# PecanPico7.net
KiCad netlist of a schematic drawn in EAGLE
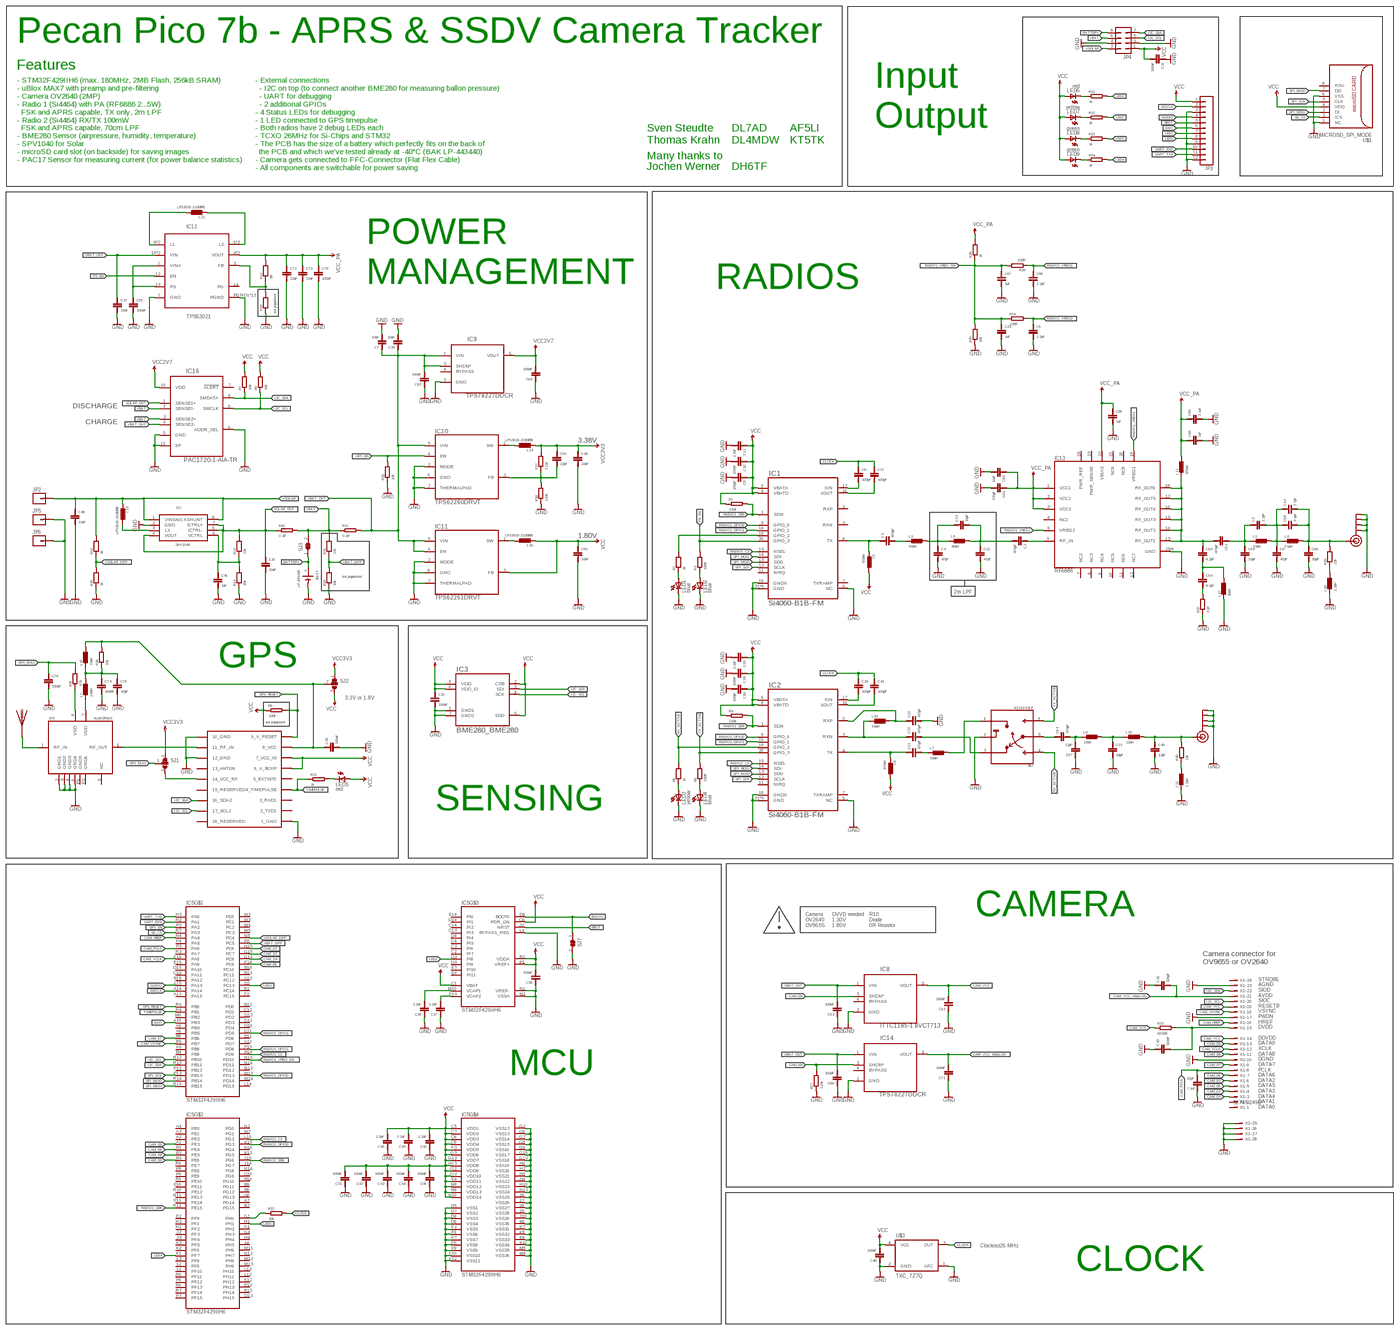
[diagram p0: schematic, sheet 1, overview]
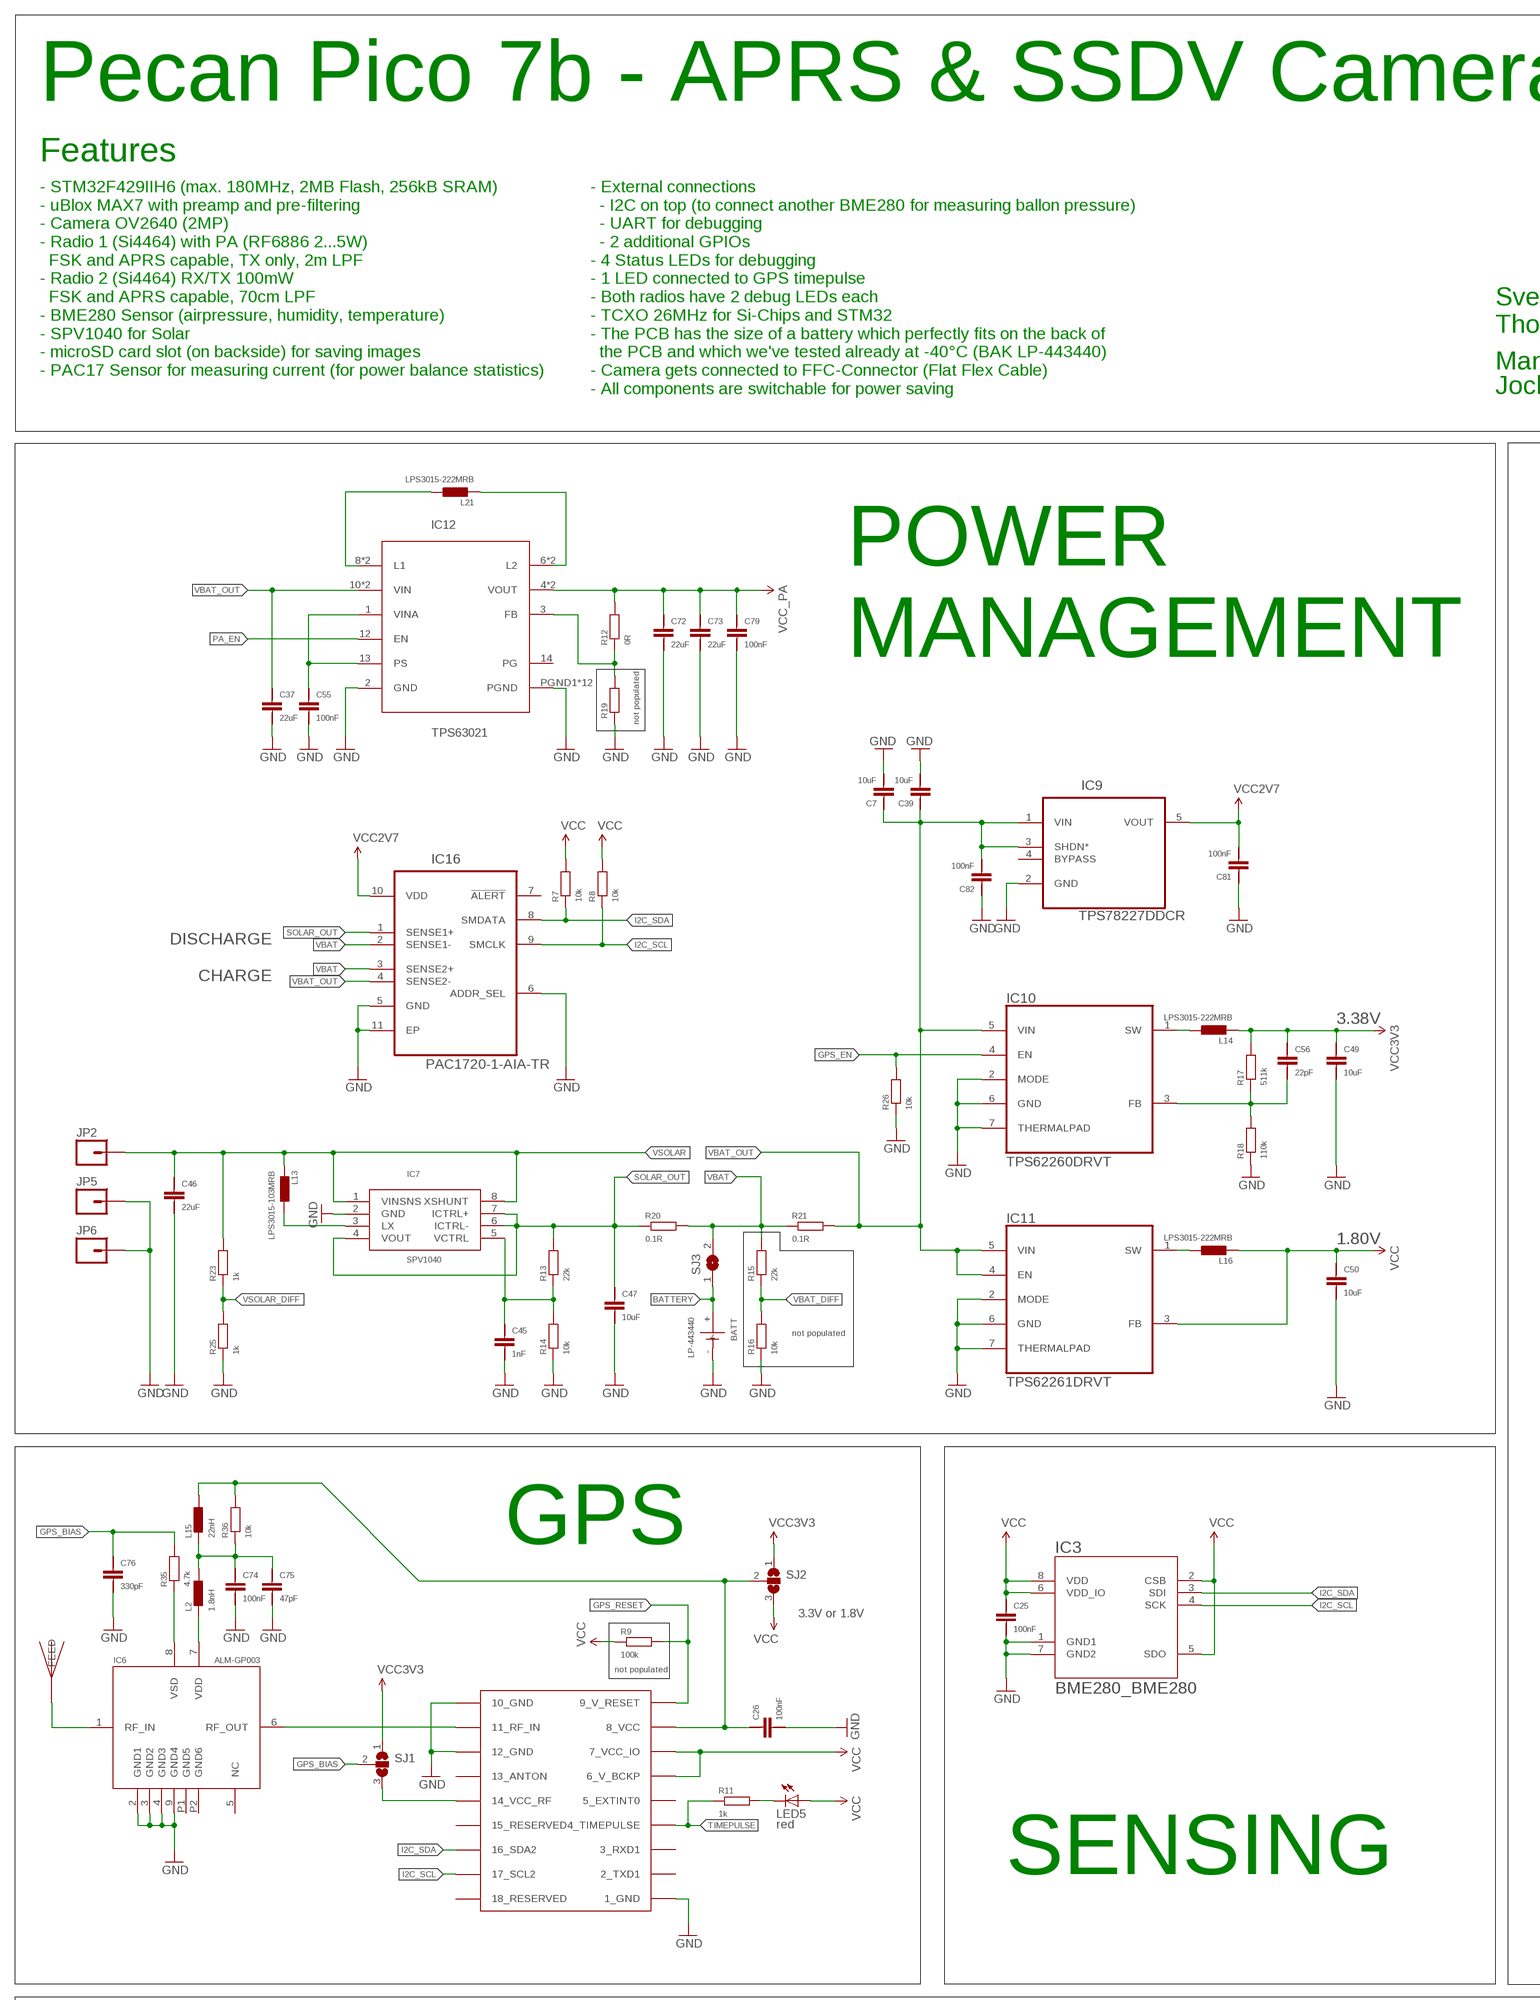
[diagram p1: schematic, sheet 1, part 1 of 4]
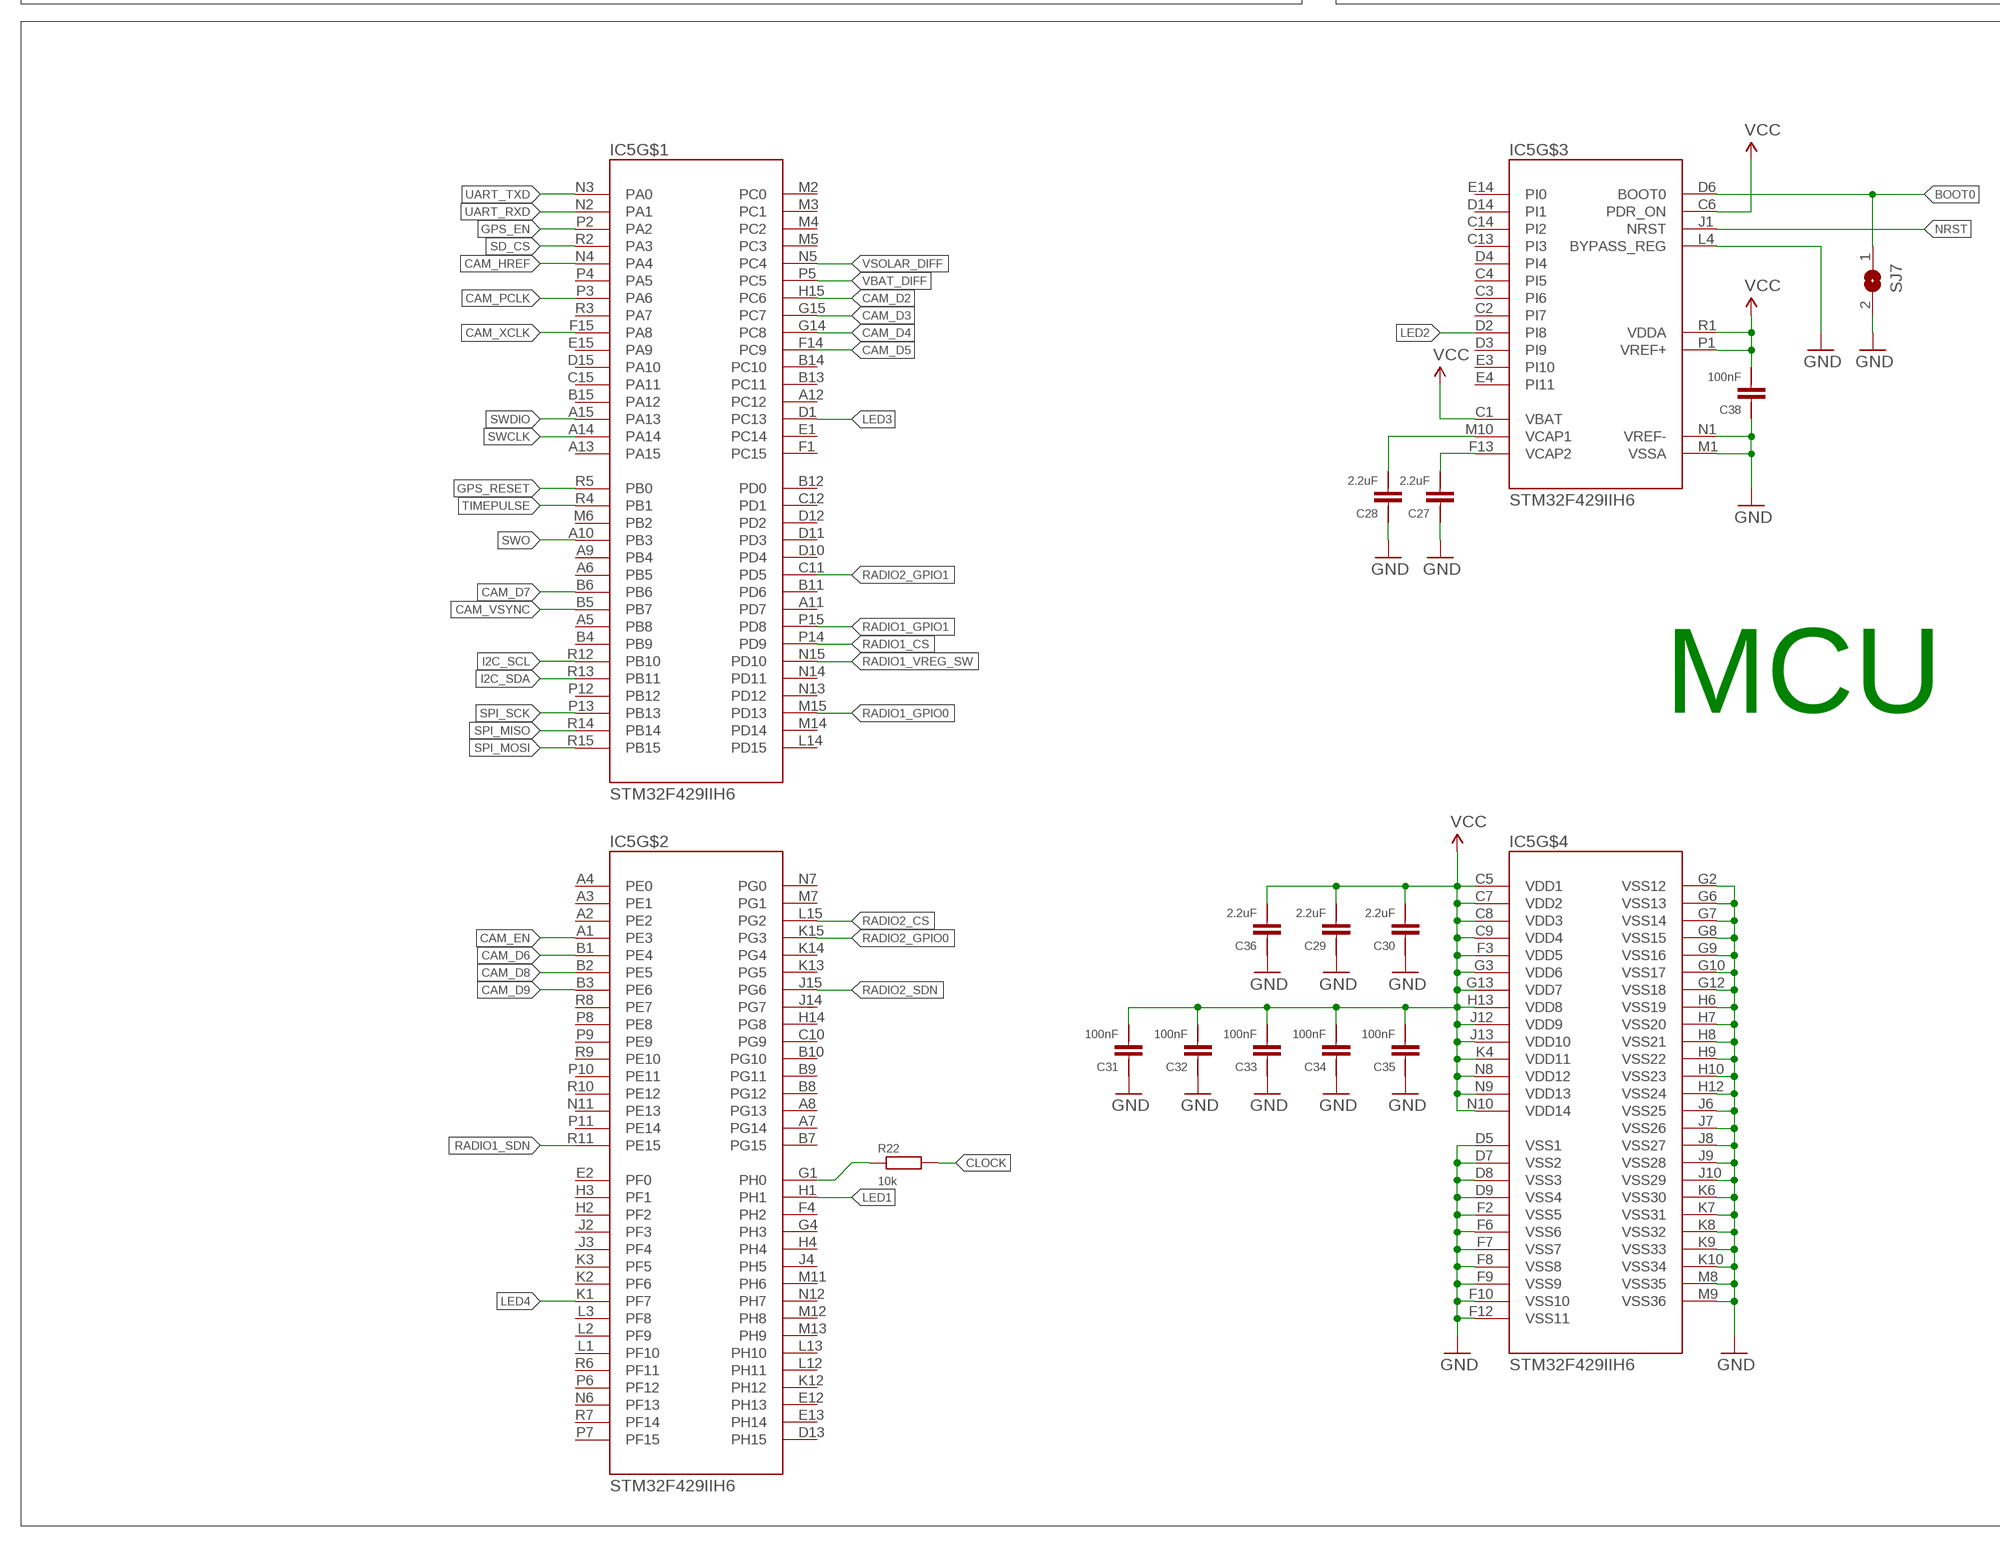
[diagram p2: schematic, sheet 1, part 2 of 4]
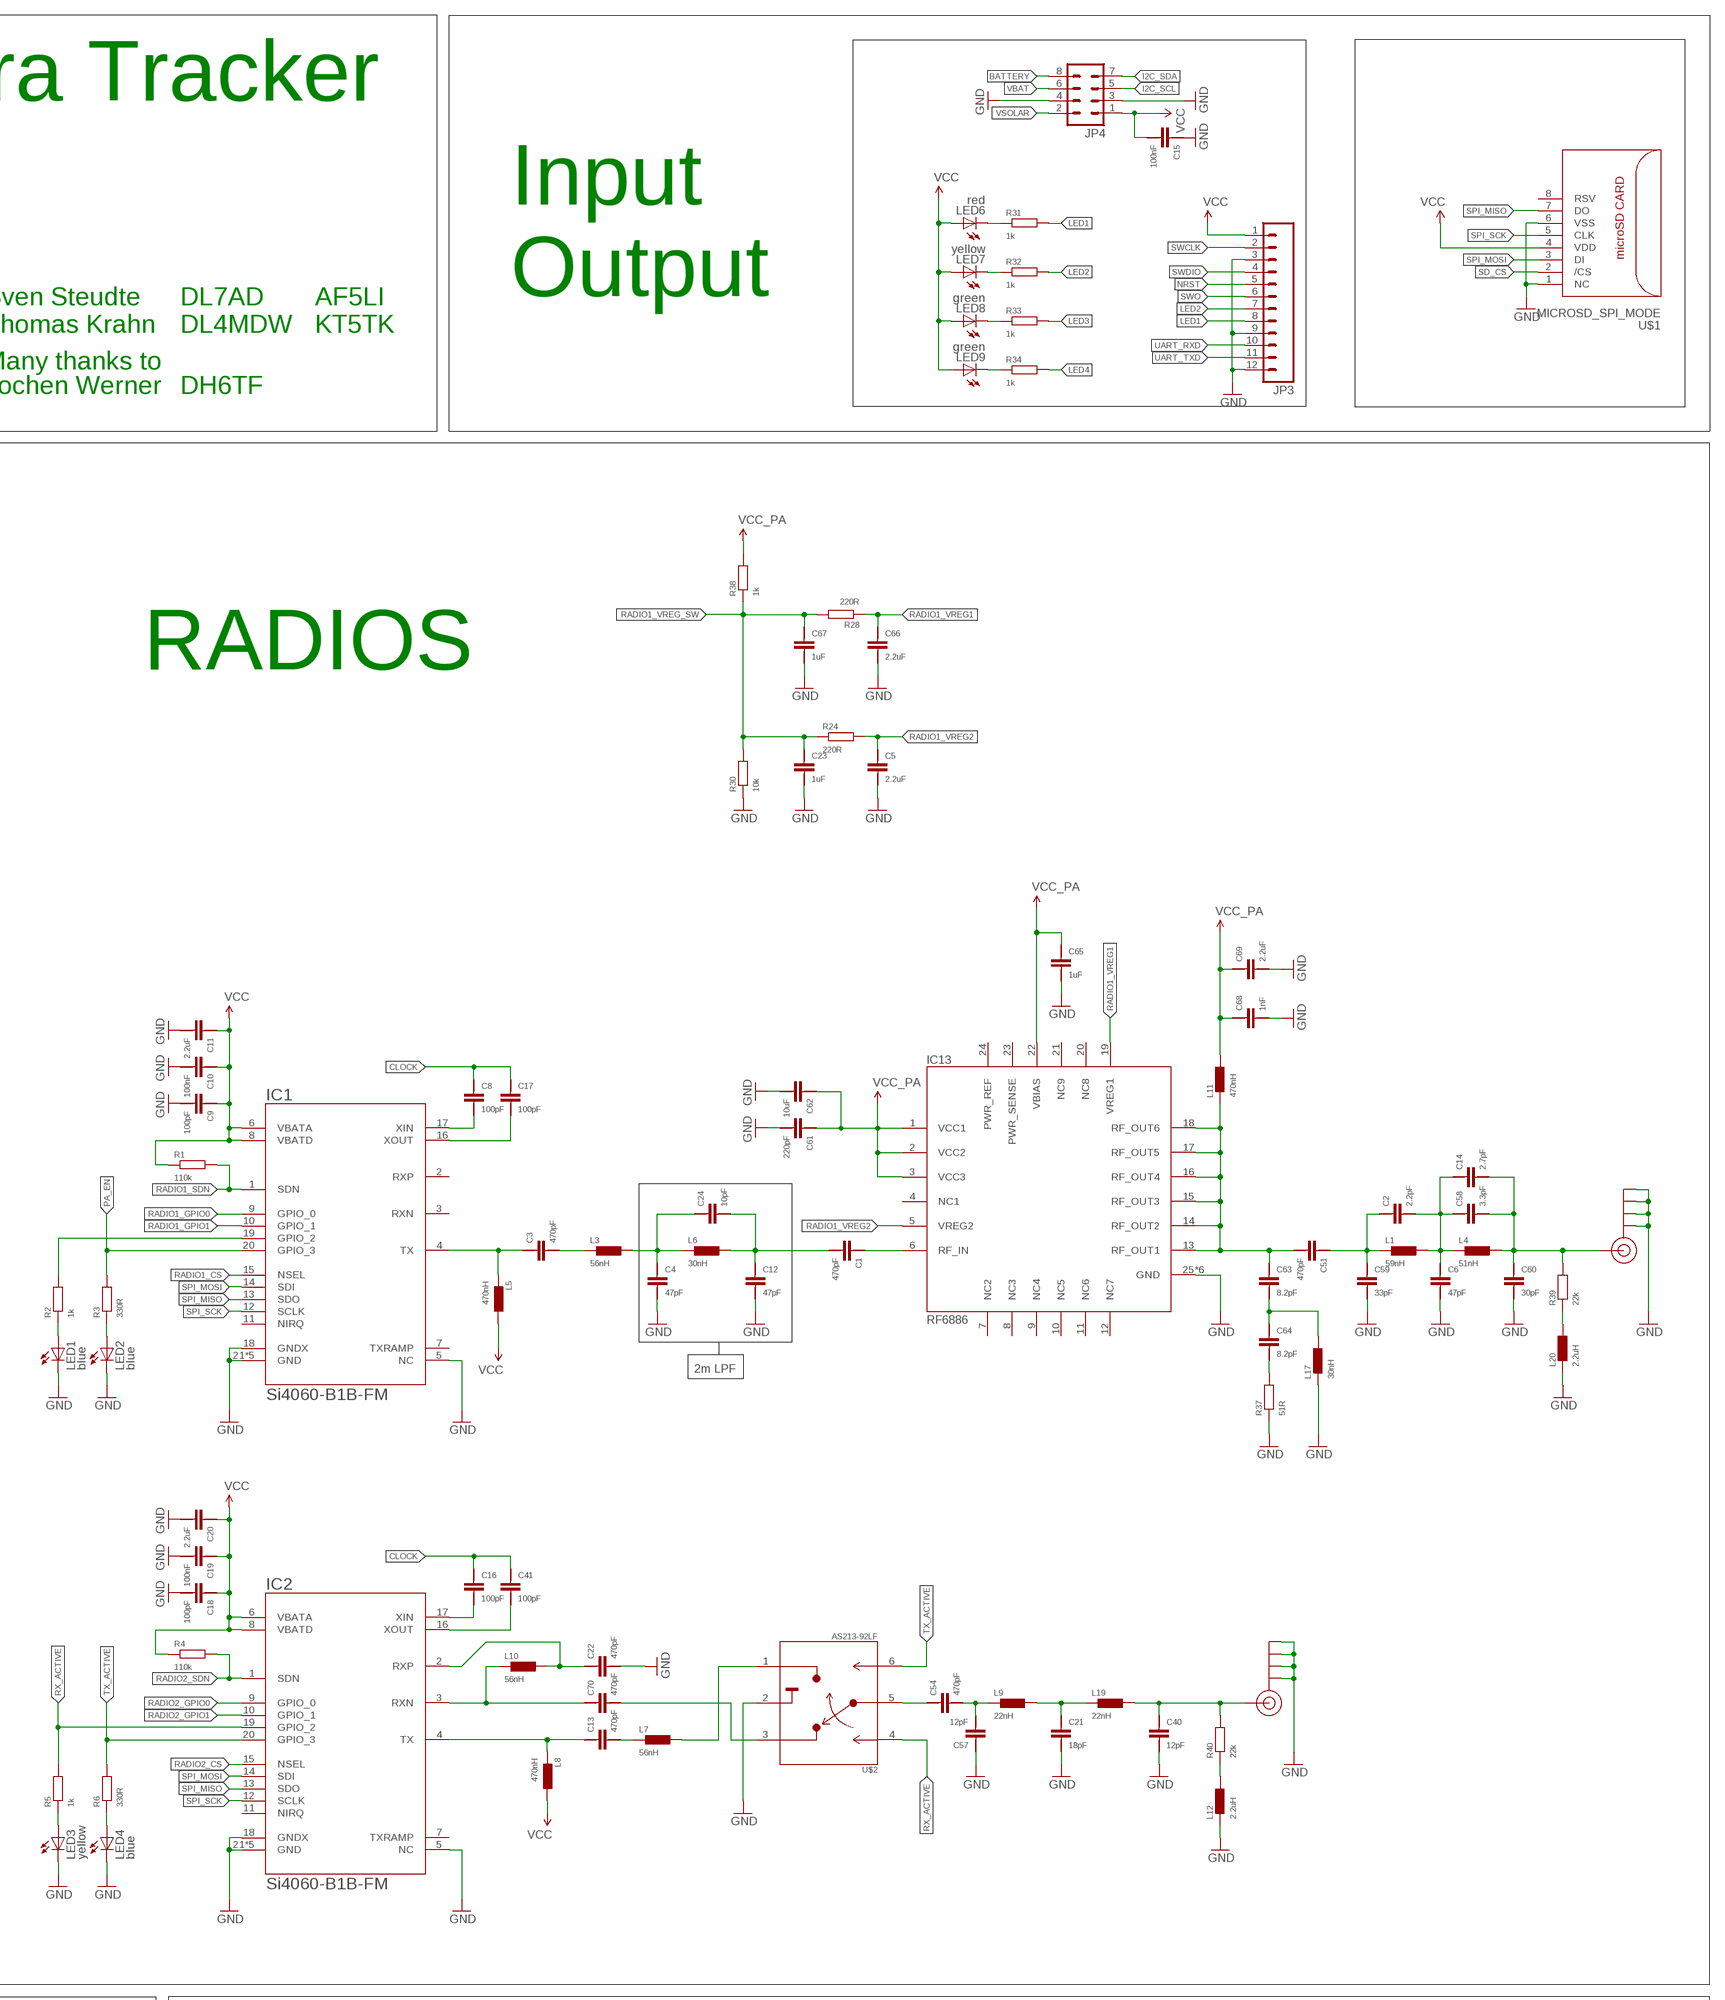
[diagram p3: schematic, sheet 1, part 3 of 4]
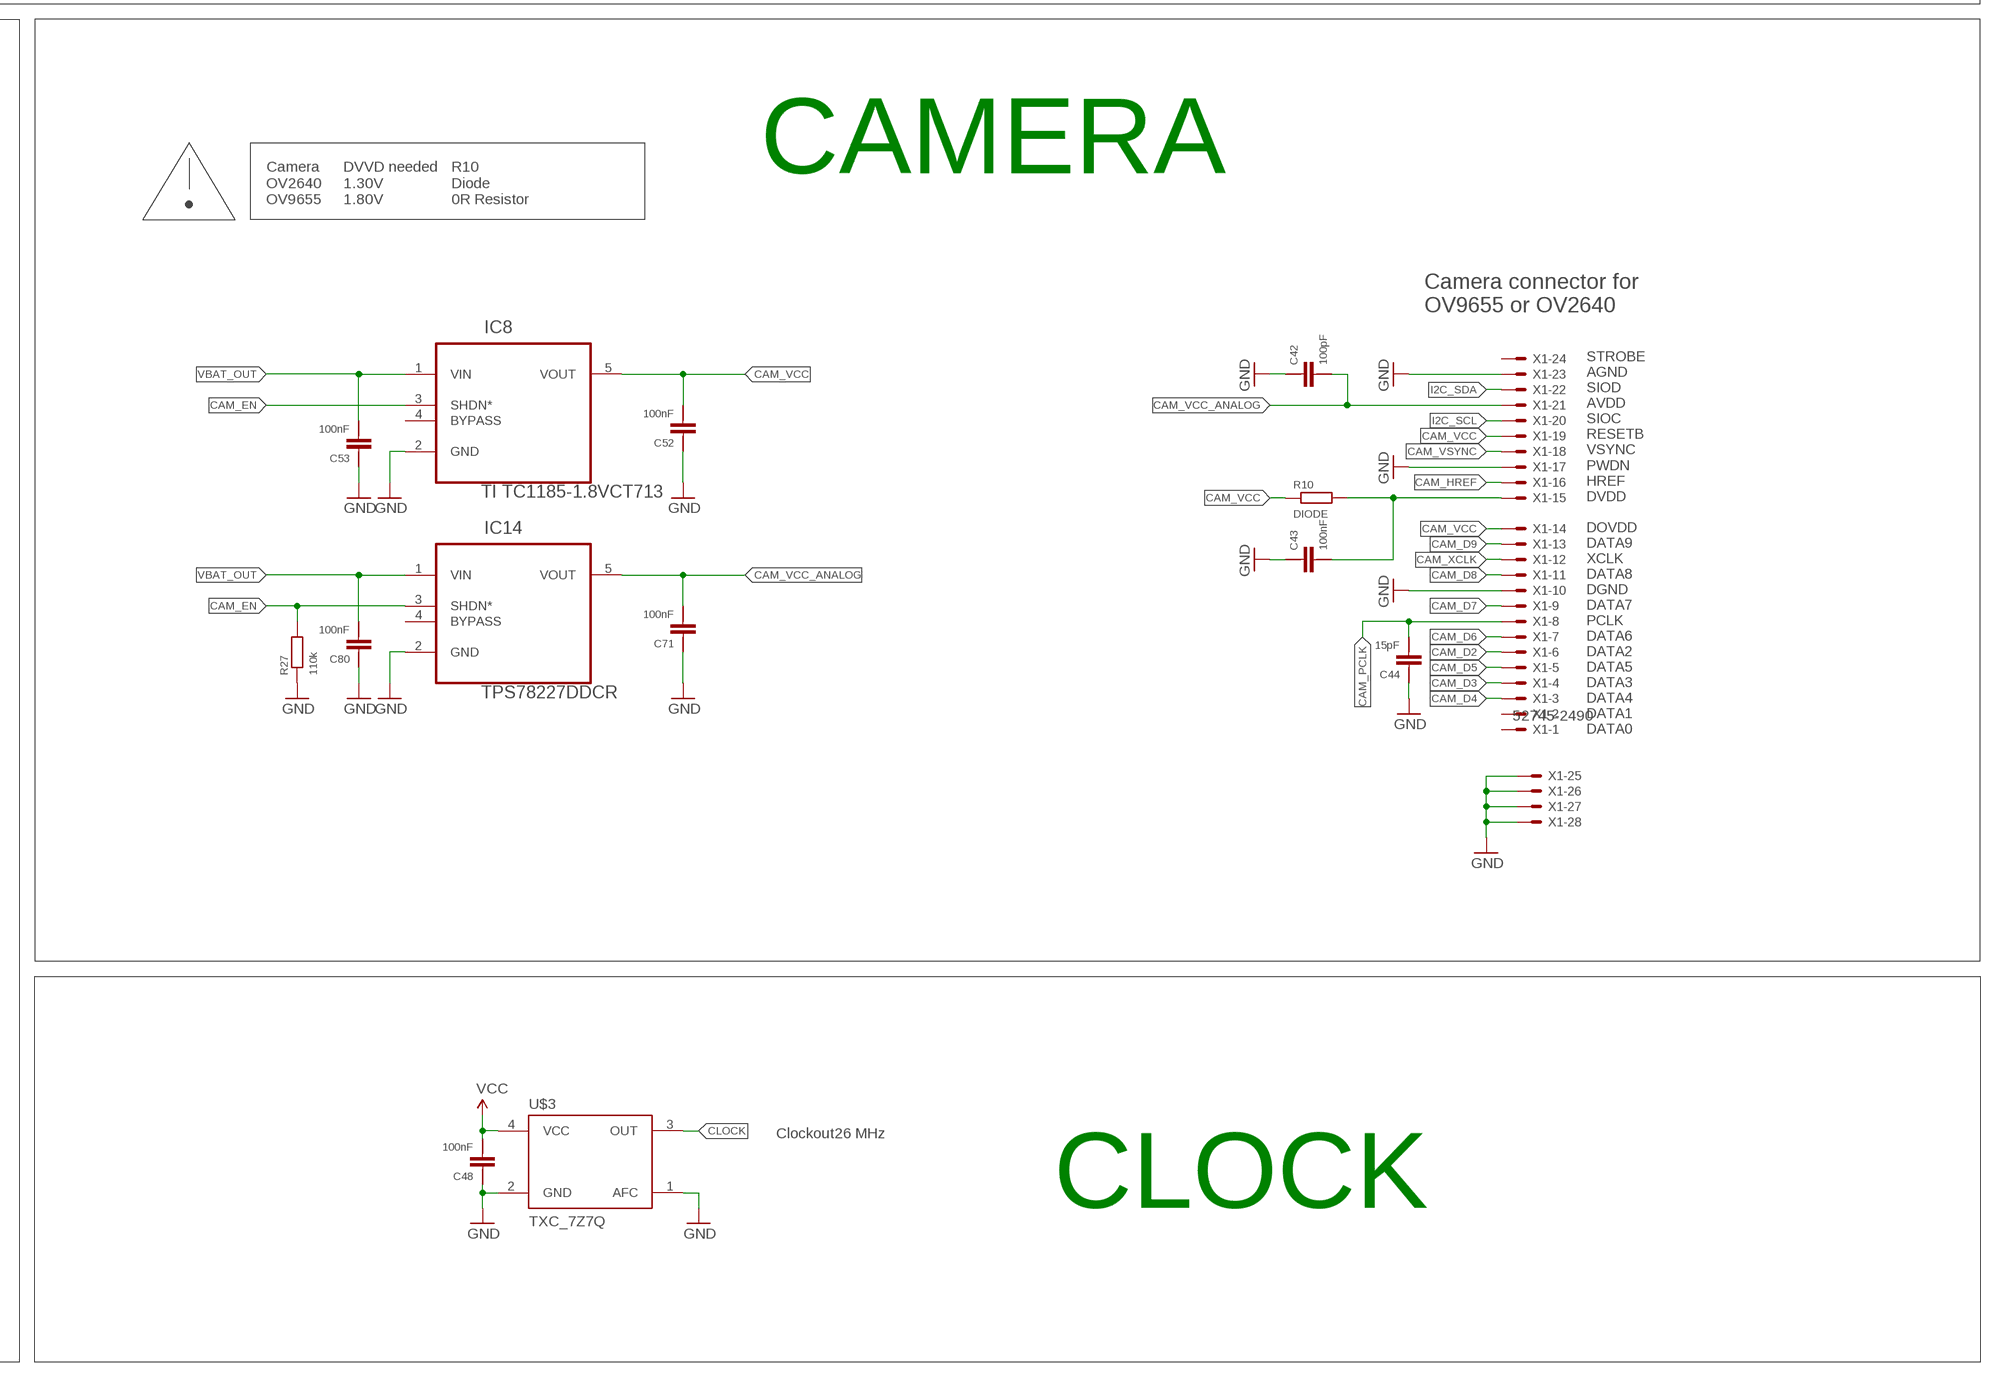
[diagram p4: schematic, sheet 1, part 4 of 4]

(export (version "E")
  (design (tool "Eeschema 10.0.6"))
  (components
    (comp (ref "BATT")
      (value "LP-443440")
      (footprint "eagle-import:LP-443440")
      (libsource (lib "eagle-import") (part "LP-443440"))
    )
    (comp (ref "C1")
      (value "470pF")
      (footprint "eagle-import:0402")
      (libsource (lib "eagle-import") (part "CAP-0402"))
    )
    (comp (ref "C2")
      (value "2.2pF")
      (footprint "eagle-import:0402")
      (libsource (lib "eagle-import") (part "CAP-0402"))
    )
    (comp (ref "C3")
      (value "470pF")
      (footprint "eagle-import:0402")
      (libsource (lib "eagle-import") (part "CAP-0402"))
    )
    (comp (ref "C4")
      (value "47pF")
      (footprint "eagle-import:0402")
      (libsource (lib "eagle-import") (part "CAP-0402"))
    )
    (comp (ref "C5")
      (value "2.2uF")
      (footprint "eagle-import:0402")
      (libsource (lib "eagle-import") (part "CAP-0402"))
    )
    (comp (ref "C6")
      (value "47pF")
      (footprint "eagle-import:0402")
      (libsource (lib "eagle-import") (part "CAP-0402"))
    )
    (comp (ref "C7")
      (value "10uF")
      (footprint "eagle-import:0805")
      (libsource (lib "eagle-import") (part "CAP-0805"))
    )
    (comp (ref "C8")
      (value "100pF")
      (footprint "eagle-import:0402")
      (libsource (lib "eagle-import") (part "CAP-0402"))
    )
    (comp (ref "C9")
      (value "100pF")
      (footprint "eagle-import:0402")
      (libsource (lib "eagle-import") (part "CAP-0402"))
    )
    (comp (ref "C10")
      (value "100nF")
      (footprint "eagle-import:0402")
      (libsource (lib "eagle-import") (part "CAP-0402"))
    )
    (comp (ref "C11")
      (value "2.2uF")
      (footprint "eagle-import:0402")
      (libsource (lib "eagle-import") (part "CAP-0402"))
    )
    (comp (ref "C12")
      (value "47pF")
      (footprint "eagle-import:0402")
      (libsource (lib "eagle-import") (part "CAP-0402"))
    )
    (comp (ref "C13")
      (value "470pF")
      (footprint "eagle-import:0402")
      (libsource (lib "eagle-import") (part "CAP-0402"))
    )
    (comp (ref "C14")
      (value "2.7pF")
      (footprint "eagle-import:0402")
      (libsource (lib "eagle-import") (part "CAP-0402"))
    )
    (comp (ref "C15")
      (value "100nF")
      (footprint "eagle-import:0402")
      (libsource (lib "eagle-import") (part "CAP-0402"))
    )
    (comp (ref "C16")
      (value "100pF")
      (footprint "eagle-import:0402")
      (libsource (lib "eagle-import") (part "CAP-0402"))
    )
    (comp (ref "C17")
      (value "100pF")
      (footprint "eagle-import:0402")
      (libsource (lib "eagle-import") (part "CAP-0402"))
    )
    (comp (ref "C18")
      (value "100pF")
      (footprint "eagle-import:0402")
      (libsource (lib "eagle-import") (part "CAP-0402"))
    )
    (comp (ref "C19")
      (value "100nF")
      (footprint "eagle-import:0402")
      (libsource (lib "eagle-import") (part "CAP-0402"))
    )
    (comp (ref "C20")
      (value "2.2uF")
      (footprint "eagle-import:0402")
      (libsource (lib "eagle-import") (part "CAP-0402"))
    )
    (comp (ref "C21")
      (value "18pF")
      (footprint "eagle-import:0402")
      (libsource (lib "eagle-import") (part "CAP-0402"))
    )
    (comp (ref "C22")
      (value "470pF")
      (footprint "eagle-import:0402")
      (libsource (lib "eagle-import") (part "CAP-0402"))
    )
    (comp (ref "C23")
      (value "1uF")
      (footprint "eagle-import:0402")
      (libsource (lib "eagle-import") (part "CAP-0402"))
    )
    (comp (ref "C24")
      (value "10pF")
      (footprint "eagle-import:0402")
      (libsource (lib "eagle-import") (part "CAP-0402"))
    )
    (comp (ref "C25")
      (value "100nF")
      (footprint "eagle-import:0402")
      (libsource (lib "eagle-import") (part "CAP-0402"))
    )
    (comp (ref "C26")
      (value "100nF")
      (footprint "eagle-import:0402")
      (libsource (lib "eagle-import") (part "CAP-0402"))
    )
    (comp (ref "C27")
      (value "2.2uF")
      (footprint "eagle-import:0402")
      (libsource (lib "eagle-import") (part "CAP-0402"))
    )
    (comp (ref "C28")
      (value "2.2uF")
      (footprint "eagle-import:0402")
      (libsource (lib "eagle-import") (part "CAP-0402"))
    )
    (comp (ref "C29")
      (value "2.2uF")
      (footprint "eagle-import:0402")
      (libsource (lib "eagle-import") (part "CAP-0402"))
    )
    (comp (ref "C30")
      (value "2.2uF")
      (footprint "eagle-import:0402")
      (libsource (lib "eagle-import") (part "CAP-0402"))
    )
    (comp (ref "C31")
      (value "100nF")
      (footprint "eagle-import:0402")
      (libsource (lib "eagle-import") (part "CAP-0402"))
    )
    (comp (ref "C32")
      (value "100nF")
      (footprint "eagle-import:0402")
      (libsource (lib "eagle-import") (part "CAP-0402"))
    )
    (comp (ref "C33")
      (value "100nF")
      (footprint "eagle-import:0402")
      (libsource (lib "eagle-import") (part "CAP-0402"))
    )
    (comp (ref "C34")
      (value "100nF")
      (footprint "eagle-import:0402")
      (libsource (lib "eagle-import") (part "CAP-0402"))
    )
    (comp (ref "C35")
      (value "100nF")
      (footprint "eagle-import:0402")
      (libsource (lib "eagle-import") (part "CAP-0402"))
    )
    (comp (ref "C36")
      (value "2.2uF")
      (footprint "eagle-import:0402")
      (libsource (lib "eagle-import") (part "CAP-0402"))
    )
    (comp (ref "C37")
      (value "22uF")
      (footprint "eagle-import:0805")
      (libsource (lib "eagle-import") (part "CAP-0805"))
    )
    (comp (ref "C38")
      (value "100nF")
      (footprint "eagle-import:0402")
      (libsource (lib "eagle-import") (part "CAP-0402"))
    )
    (comp (ref "C39")
      (value "10uF")
      (footprint "eagle-import:0805")
      (libsource (lib "eagle-import") (part "CAP-0805"))
    )
    (comp (ref "C40")
      (value "12pF")
      (footprint "eagle-import:0402")
      (libsource (lib "eagle-import") (part "CAP-0402"))
    )
    (comp (ref "C41")
      (value "100pF")
      (footprint "eagle-import:0402")
      (libsource (lib "eagle-import") (part "CAP-0402"))
    )
    (comp (ref "C42")
      (value "100pF")
      (footprint "eagle-import:0402")
      (libsource (lib "eagle-import") (part "CAP-0402"))
    )
    (comp (ref "C43")
      (value "100nF")
      (footprint "eagle-import:0402")
      (libsource (lib "eagle-import") (part "CAP-0402"))
    )
    (comp (ref "C44")
      (value "15pF")
      (footprint "eagle-import:0402")
      (libsource (lib "eagle-import") (part "CAP-0402"))
    )
    (comp (ref "C45")
      (value "1nF")
      (footprint "eagle-import:0402")
      (libsource (lib "eagle-import") (part "CAP-0402"))
    )
    (comp (ref "C46")
      (value "22uF")
      (footprint "eagle-import:0805")
      (libsource (lib "eagle-import") (part "CAP-0805"))
    )
    (comp (ref "C47")
      (value "10uF")
      (footprint "eagle-import:0805")
      (libsource (lib "eagle-import") (part "CAP-0805"))
    )
    (comp (ref "C48")
      (value "100nF")
      (footprint "eagle-import:0402")
      (libsource (lib "eagle-import") (part "CAP-0402"))
    )
    (comp (ref "C49")
      (value "10uF")
      (footprint "eagle-import:0805")
      (libsource (lib "eagle-import") (part "CAP-0805"))
    )
    (comp (ref "C50")
      (value "10uF")
      (footprint "eagle-import:0805")
      (libsource (lib "eagle-import") (part "CAP-0805"))
    )
    (comp (ref "C51")
      (value "470pF")
      (footprint "eagle-import:0402")
      (libsource (lib "eagle-import") (part "CAP-0402"))
    )
    (comp (ref "C52")
      (value "100nF")
      (footprint "eagle-import:0402")
      (libsource (lib "eagle-import") (part "CAP-0402"))
    )
    (comp (ref "C53")
      (value "100nF")
      (footprint "eagle-import:0402")
      (libsource (lib "eagle-import") (part "CAP-0402"))
    )
    (comp (ref "C54")
      (value "470pF")
      (footprint "eagle-import:0402")
      (libsource (lib "eagle-import") (part "CAP-0402"))
    )
    (comp (ref "C55")
      (value "100nF")
      (footprint "eagle-import:0402")
      (libsource (lib "eagle-import") (part "CAP-0402"))
    )
    (comp (ref "C56")
      (value "22pF")
      (footprint "eagle-import:0402")
      (libsource (lib "eagle-import") (part "CAP-0402"))
    )
    (comp (ref "C57")
      (value "12pF")
      (footprint "eagle-import:0402")
      (libsource (lib "eagle-import") (part "CAP-0402"))
    )
    (comp (ref "C58")
      (value "3.3pF")
      (footprint "eagle-import:0402")
      (libsource (lib "eagle-import") (part "CAP-0402"))
    )
    (comp (ref "C59")
      (value "33pF")
      (footprint "eagle-import:0402")
      (libsource (lib "eagle-import") (part "CAP-0402"))
    )
    (comp (ref "C60")
      (value "30pF")
      (footprint "eagle-import:0402")
      (libsource (lib "eagle-import") (part "CAP-0402"))
    )
    (comp (ref "C61")
      (value "220pF")
      (footprint "eagle-import:0402")
      (libsource (lib "eagle-import") (part "CAP-0402"))
    )
    (comp (ref "C62")
      (value "10uF")
      (footprint "eagle-import:0805")
      (libsource (lib "eagle-import") (part "CAP-0805"))
    )
    (comp (ref "C63")
      (value "8.2pF")
      (footprint "eagle-import:0402")
      (libsource (lib "eagle-import") (part "CAP-0402"))
    )
    (comp (ref "C64")
      (value "8.2pF")
      (footprint "eagle-import:0402")
      (libsource (lib "eagle-import") (part "CAP-0402"))
    )
    (comp (ref "C65")
      (value "1uF")
      (footprint "eagle-import:0402")
      (libsource (lib "eagle-import") (part "CAP-0402"))
    )
    (comp (ref "C66")
      (value "2.2uF")
      (footprint "eagle-import:0402")
      (libsource (lib "eagle-import") (part "CAP-0402"))
    )
    (comp (ref "C67")
      (value "1uF")
      (footprint "eagle-import:0402")
      (libsource (lib "eagle-import") (part "CAP-0402"))
    )
    (comp (ref "C68")
      (value "1nF")
      (footprint "eagle-import:0402")
      (libsource (lib "eagle-import") (part "CAP-0402"))
    )
    (comp (ref "C69")
      (value "2.2uF")
      (footprint "eagle-import:0402")
      (libsource (lib "eagle-import") (part "CAP-0402"))
    )
    (comp (ref "C70")
      (value "470pF")
      (footprint "eagle-import:0402")
      (libsource (lib "eagle-import") (part "CAP-0402"))
    )
    (comp (ref "C71")
      (value "100nF")
      (footprint "eagle-import:0402")
      (libsource (lib "eagle-import") (part "CAP-0402"))
    )
    (comp (ref "C72")
      (value "22uF")
      (footprint "eagle-import:0805")
      (libsource (lib "eagle-import") (part "CAP-0805"))
    )
    (comp (ref "C73")
      (value "22uF")
      (footprint "eagle-import:0805")
      (libsource (lib "eagle-import") (part "CAP-0805"))
    )
    (comp (ref "C74")
      (value "100nF")
      (footprint "eagle-import:0402")
      (libsource (lib "eagle-import") (part "CAP-0402"))
    )
    (comp (ref "C75")
      (value "47pF")
      (footprint "eagle-import:0402")
      (libsource (lib "eagle-import") (part "CAP-0402"))
    )
    (comp (ref "C76")
      (value "330pF")
      (footprint "eagle-import:0402")
      (libsource (lib "eagle-import") (part "CAP-0402"))
    )
    (comp (ref "C79")
      (value "100nF")
      (footprint "eagle-import:0402")
      (libsource (lib "eagle-import") (part "CAP-0402"))
    )
    (comp (ref "C80")
      (value "100nF")
      (footprint "eagle-import:0402")
      (libsource (lib "eagle-import") (part "CAP-0402"))
    )
    (comp (ref "C81")
      (value "100nF")
      (footprint "eagle-import:0402")
      (libsource (lib "eagle-import") (part "CAP-0402"))
    )
    (comp (ref "C82")
      (value "100nF")
      (footprint "eagle-import:0402")
      (libsource (lib "eagle-import") (part "CAP-0402"))
    )
    (comp (ref "IC1")
      (value "Si4060-B1B-FM")
      (footprint "eagle-import:QFN-20")
      (libsource (lib "eagle-import") (part "SI4463/4"))
    )
    (comp (ref "IC2")
      (value "Si4060-B1B-FM")
      (footprint "eagle-import:QFN-20")
      (libsource (lib "eagle-import") (part "SI4463/4"))
    )
    (comp (ref "IC3")
      (value "BME280_BME280")
      (footprint "eagle-import:BME280_BME280")
      (libsource (lib "eagle-import") (part "BME280_BME280"))
    )
    (comp (ref "IC4")
      (value "uBlox MAX7/8")
      (footprint "eagle-import:UBLOX_MAX-6")
      (libsource (lib "eagle-import") (part "UBLOX_MAX-6"))
    )
    (comp (ref "IC5")
      (value "STM32F429IIH6")
      (footprint "eagle-import:UFBGA176")
      (libsource (lib "eagle-import") (part "STM32F429IIH6"))
    )
    (comp (ref "IC6")
      (value "ALM-GP003")
      (footprint "eagle-import:ALM-GP003")
      (libsource (lib "eagle-import") (part "ALM-GP003"))
    )
    (comp (ref "IC7")
      (value "SPV1040")
      (footprint "eagle-import:TSSOP8")
      (libsource (lib "eagle-import") (part "SPV1040"))
    )
    (comp (ref "IC8")
      (value "TI TC1185-1.8VCT713")
      (footprint "eagle-import:SOT95P290X145-5N")
      (fields (field (name "MPN") "TC1185-1.8VCT713"))
      (libsource (lib "eagle-import") (part "TC1185-1.8VCT713"))
    )
    (comp (ref "IC9")
      (value "TPS78227DDCR")
      (footprint "eagle-import:SOT95P290X145-5N")
      (fields (field (name "MPN") "TC1185-1.8VCT713"))
      (libsource (lib "eagle-import") (part "TC1185-1.8VCT713"))
    )
    (comp (ref "IC10")
      (value "TPS62260DRVT")
      (footprint "eagle-import:SON65P210X210X80-7N")
      (libsource (lib "eagle-import") (part "TPS62260DRVT"))
    )
    (comp (ref "IC11")
      (value "TPS62261DRVT")
      (footprint "eagle-import:SON65P210X210X80-7N")
      (fields (field (name "MPN") "TPS62260DRVT"))
      (libsource (lib "eagle-import") (part "TPS62260DRVT"))
    )
    (comp (ref "IC12")
      (value "TPS63021")
      (footprint "eagle-import:QFN-14")
      (libsource (lib "eagle-import") (part "TPS63020"))
    )
    (comp (ref "IC13")
      (value "RF6886")
      (footprint "eagle-import:QFN-24")
      (libsource (lib "eagle-import") (part "RF6886"))
    )
    (comp (ref "IC14")
      (value "TPS78227DDCR")
      (footprint "eagle-import:SOT95P290X145-5N")
      (fields (field (name "MPN") "TC1185-1.8VCT713"))
      (libsource (lib "eagle-import") (part "TC1185-1.8VCT713"))
    )
    (comp (ref "IC16")
      (value "PAC1720-1-AIA-TR")
      (footprint "eagle-import:DFN300X300X90-11N")
      (libsource (lib "eagle-import") (part "PAC1720-1-AIA-TR"))
    )
    (comp (ref "J$1")
      (value "SMA_EDGE")
      (footprint "eagle-import:SMA-EDGE")
      (libsource (lib "eagle-import") (part "SMA_EDGE"))
    )
    (comp (ref "J$2")
      (value "SMA_EDGE")
      (footprint "eagle-import:SMA-EDGE")
      (libsource (lib "eagle-import") (part "SMA_EDGE"))
    )
    (comp (ref "JP2")
      (value "M01SMD")
      (footprint "eagle-import:LUXEON-PAD")
      (libsource (lib "eagle-import") (part "M01SMD"))
    )
    (comp (ref "JP3")
      (value "M12PTH")
      (footprint "eagle-import:1X12")
      (libsource (lib "eagle-import") (part "M12PTH"))
    )
    (comp (ref "JP4")
      (value "M04X2SMD")
      (footprint "eagle-import:2X4_2")
      (libsource (lib "eagle-import") (part "M04X2SMD"))
    )
    (comp (ref "JP5")
      (value "M01SMD")
      (footprint "eagle-import:LUXEON-PAD")
      (libsource (lib "eagle-import") (part "M01SMD"))
    )
    (comp (ref "JP6")
      (value "M01SMD")
      (footprint "eagle-import:LUXEON-PAD")
      (libsource (lib "eagle-import") (part "M01SMD"))
    )
    (comp (ref "L1")
      (value "59nH")
      (footprint "eagle-import:0603@1")
      (libsource (lib "eagle-import") (part "IND-04020603"))
    )
    (comp (ref "L2")
      (value "1.8nH")
      (footprint "eagle-import:0402")
      (libsource (lib "eagle-import") (part "IND-0402"))
    )
    (comp (ref "L3")
      (value "56nH")
      (footprint "eagle-import:0402")
      (libsource (lib "eagle-import") (part "IND-0402"))
    )
    (comp (ref "L4")
      (value "51nH")
      (footprint "eagle-import:0603@1")
      (libsource (lib "eagle-import") (part "IND-04020603"))
    )
    (comp (ref "L5")
      (value "470nH")
      (footprint "eagle-import:0805@1")
      (libsource (lib "eagle-import") (part "IND-04020805"))
    )
    (comp (ref "L6")
      (value "30nH")
      (footprint "eagle-import:0402")
      (libsource (lib "eagle-import") (part "IND-0402"))
    )
    (comp (ref "L7")
      (value "56nH")
      (footprint "eagle-import:0402")
      (libsource (lib "eagle-import") (part "IND-0402"))
    )
    (comp (ref "L8")
      (value "470nH")
      (footprint "eagle-import:0805@1")
      (libsource (lib "eagle-import") (part "IND-04020805"))
    )
    (comp (ref "L9")
      (value "22nH")
      (footprint "eagle-import:0402")
      (libsource (lib "eagle-import") (part "IND-0402"))
    )
    (comp (ref "L10")
      (value "56nH")
      (footprint "eagle-import:0402")
      (libsource (lib "eagle-import") (part "IND-0402"))
    )
    (comp (ref "L11")
      (value "470nH")
      (footprint "eagle-import:0805@1")
      (libsource (lib "eagle-import") (part "IND-04020805"))
    )
    (comp (ref "L12")
      (value "2.2uH")
      (footprint "eagle-import:0402")
      (libsource (lib "eagle-import") (part "IND-0402"))
    )
    (comp (ref "L13")
      (value "LPS3015-103MRB")
      (footprint "eagle-import:LPS3015")
      (libsource (lib "eagle-import") (part "IND-LPS3015"))
    )
    (comp (ref "L14")
      (value "LPS3015-222MRB")
      (footprint "eagle-import:LPS3015")
      (libsource (lib "eagle-import") (part "IND-LPS3015"))
    )
    (comp (ref "L15")
      (value "22nH")
      (footprint "eagle-import:0402")
      (libsource (lib "eagle-import") (part "IND-0402"))
    )
    (comp (ref "L16")
      (value "LPS3015-222MRB")
      (footprint "eagle-import:LPS3015")
      (libsource (lib "eagle-import") (part "IND-LPS3015"))
    )
    (comp (ref "L17")
      (value "30nH")
      (footprint "eagle-import:0603@1")
      (libsource (lib "eagle-import") (part "IND-04020603"))
    )
    (comp (ref "L19")
      (value "22nH")
      (footprint "eagle-import:0402")
      (libsource (lib "eagle-import") (part "IND-0402"))
    )
    (comp (ref "L20")
      (value "2.2uH")
      (footprint "eagle-import:0402")
      (libsource (lib "eagle-import") (part "IND-0402"))
    )
    (comp (ref "L21")
      (value "LPS3015-222MRB")
      (footprint "eagle-import:LPS3015")
      (libsource (lib "eagle-import") (part "IND-LPS3015"))
    )
    (comp (ref "LED1")
      (value "blue")
      (footprint "eagle-import:LED-0603")
      (libsource (lib "eagle-import") (part "LED0603"))
    )
    (comp (ref "LED2")
      (value "blue")
      (footprint "eagle-import:LED-0603")
      (libsource (lib "eagle-import") (part "LED0603"))
    )
    (comp (ref "LED3")
      (value "yellow")
      (footprint "eagle-import:LED-0603")
      (libsource (lib "eagle-import") (part "LED0603"))
    )
    (comp (ref "LED4")
      (value "blue")
      (footprint "eagle-import:LED-0603")
      (libsource (lib "eagle-import") (part "LED0603"))
    )
    (comp (ref "LED5")
      (value "red")
      (footprint "eagle-import:LED-0603")
      (libsource (lib "eagle-import") (part "LED0603"))
    )
    (comp (ref "LED6")
      (value "red")
      (footprint "eagle-import:LED-0603")
      (libsource (lib "eagle-import") (part "LED0603"))
    )
    (comp (ref "LED7")
      (value "yellow")
      (footprint "eagle-import:LED-0603")
      (libsource (lib "eagle-import") (part "LED0603"))
    )
    (comp (ref "LED8")
      (value "green")
      (footprint "eagle-import:LED-0603")
      (libsource (lib "eagle-import") (part "LED0603"))
    )
    (comp (ref "LED9")
      (value "green")
      (footprint "eagle-import:LED-0603")
      (libsource (lib "eagle-import") (part "LED0603"))
    )
    (comp (ref "R1")
      (value "110k")
      (footprint "eagle-import:0402")
      (libsource (lib "eagle-import") (part "RES-0402"))
    )
    (comp (ref "R2")
      (value "1k")
      (footprint "eagle-import:0402")
      (libsource (lib "eagle-import") (part "RES-0402"))
    )
    (comp (ref "R3")
      (value "330R")
      (footprint "eagle-import:0402")
      (libsource (lib "eagle-import") (part "RES-0402"))
    )
    (comp (ref "R4")
      (value "110k")
      (footprint "eagle-import:0402")
      (libsource (lib "eagle-import") (part "RES-0402"))
    )
    (comp (ref "R5")
      (value "1k")
      (footprint "eagle-import:0402")
      (libsource (lib "eagle-import") (part "RES-0402"))
    )
    (comp (ref "R6")
      (value "330R")
      (footprint "eagle-import:0402")
      (libsource (lib "eagle-import") (part "RES-0402"))
    )
    (comp (ref "R7")
      (value "10k")
      (footprint "eagle-import:0402")
      (libsource (lib "eagle-import") (part "RES-0402"))
    )
    (comp (ref "R8")
      (value "10k")
      (footprint "eagle-import:0402")
      (libsource (lib "eagle-import") (part "RES-0402"))
    )
    (comp (ref "R9")
      (value "100k")
      (footprint "eagle-import:0402")
      (libsource (lib "eagle-import") (part "RES-0402"))
    )
    (comp (ref "R10")
      (value "DIODE")
      (footprint "eagle-import:0402")
      (libsource (lib "eagle-import") (part "RES-0402"))
    )
    (comp (ref "R11")
      (value "1k")
      (footprint "eagle-import:0402")
      (libsource (lib "eagle-import") (part "RES-0402"))
    )
    (comp (ref "R12")
      (value "0R")
      (footprint "eagle-import:0402")
      (libsource (lib "eagle-import") (part "RES-0402"))
    )
    (comp (ref "R13")
      (value "22k")
      (footprint "eagle-import:0402")
      (libsource (lib "eagle-import") (part "RES-0402"))
    )
    (comp (ref "R14")
      (value "10k")
      (footprint "eagle-import:0402")
      (libsource (lib "eagle-import") (part "RES-0402"))
    )
    (comp (ref "R15")
      (value "22k")
      (footprint "eagle-import:0402")
      (libsource (lib "eagle-import") (part "RES-0402"))
    )
    (comp (ref "R16")
      (value "10k")
      (footprint "eagle-import:0402")
      (libsource (lib "eagle-import") (part "RES-0402"))
    )
    (comp (ref "R17")
      (value "511k")
      (footprint "eagle-import:0402")
      (libsource (lib "eagle-import") (part "RES-0402"))
    )
    (comp (ref "R18")
      (value "110k")
      (footprint "eagle-import:0402")
      (libsource (lib "eagle-import") (part "RES-0402"))
    )
    (comp (ref "R19")
      (value "RES-0402")
      (footprint "eagle-import:0402")
      (libsource (lib "eagle-import") (part "RES-0402"))
    )
    (comp (ref "R20")
      (value "0.1R")
      (footprint "eagle-import:0603")
      (libsource (lib "eagle-import") (part "RES-04020603"))
    )
    (comp (ref "R21")
      (value "0.1R")
      (footprint "eagle-import:0603")
      (libsource (lib "eagle-import") (part "RES-04020603"))
    )
    (comp (ref "R22")
      (value "10k")
      (footprint "eagle-import:0402")
      (libsource (lib "eagle-import") (part "RES-0402"))
    )
    (comp (ref "R23")
      (value "1k")
      (footprint "eagle-import:0402")
      (libsource (lib "eagle-import") (part "RES-0402"))
    )
    (comp (ref "R24")
      (value "220R")
      (footprint "eagle-import:0402")
      (libsource (lib "eagle-import") (part "RES-0402"))
    )
    (comp (ref "R25")
      (value "1k")
      (footprint "eagle-import:0402")
      (libsource (lib "eagle-import") (part "RES-0402"))
    )
    (comp (ref "R26")
      (value "10k")
      (footprint "eagle-import:0402")
      (libsource (lib "eagle-import") (part "RES-0402"))
    )
    (comp (ref "R27")
      (value "110k")
      (footprint "eagle-import:0402")
      (libsource (lib "eagle-import") (part "RES-0402"))
    )
    (comp (ref "R28")
      (value "220R")
      (footprint "eagle-import:0402")
      (libsource (lib "eagle-import") (part "RES-0402"))
    )
    (comp (ref "R30")
      (value "10k")
      (footprint "eagle-import:0402")
      (libsource (lib "eagle-import") (part "RES-0402"))
    )
    (comp (ref "R31")
      (value "1k")
      (footprint "eagle-import:0402")
      (libsource (lib "eagle-import") (part "RES-0402"))
    )
    (comp (ref "R32")
      (value "1k")
      (footprint "eagle-import:0402")
      (libsource (lib "eagle-import") (part "RES-0402"))
    )
    (comp (ref "R33")
      (value "1k")
      (footprint "eagle-import:0402")
      (libsource (lib "eagle-import") (part "RES-0402"))
    )
    (comp (ref "R34")
      (value "1k")
      (footprint "eagle-import:0402")
      (libsource (lib "eagle-import") (part "RES-0402"))
    )
    (comp (ref "R35")
      (value "4.7k")
      (footprint "eagle-import:0402")
      (libsource (lib "eagle-import") (part "RES-0402"))
    )
    (comp (ref "R36")
      (value "10k")
      (footprint "eagle-import:0402")
      (libsource (lib "eagle-import") (part "RES-0402"))
    )
    (comp (ref "R37")
      (value "51R")
      (footprint "eagle-import:0402")
      (libsource (lib "eagle-import") (part "RES-0402"))
    )
    (comp (ref "R38")
      (value "1k")
      (footprint "eagle-import:0402")
      (libsource (lib "eagle-import") (part "RES-0402"))
    )
    (comp (ref "R39")
      (value "22k")
      (footprint "eagle-import:0402")
      (libsource (lib "eagle-import") (part "RES-0402"))
    )
    (comp (ref "R40")
      (value "22k")
      (footprint "eagle-import:0402")
      (libsource (lib "eagle-import") (part "RES-0402"))
    )
    (comp (ref "SJ1")
      (value "SJ2W")
      (footprint "eagle-import:SJ_2")
      (libsource (lib "eagle-import") (part "SJ2W"))
    )
    (comp (ref "SJ2")
      (value "SJ2W")
      (footprint "eagle-import:SJ_2")
      (libsource (lib "eagle-import") (part "SJ2W"))
    )
    (comp (ref "SJ3") (value "SJ") (footprint "eagle-import:SJ") (libsource (lib "eagle-import") (part "SJ")))
    (comp (ref "SJ7") (value "SJ") (footprint "eagle-import:SJ") (libsource (lib "eagle-import") (part "SJ")))
    (comp (ref "U$1")
      (value "MICROSD_SPI_MODE")
      (footprint "eagle-import:MICRO_SD_CONNECTOR")
      (libsource (lib "eagle-import") (part "MICROSD_SPI_MODE"))
    )
    (comp (ref "U$2")
      (value "AS213-92LF")
      (footprint "eagle-import:SC-70")
      (libsource (lib "eagle-import") (part "AS213-92LF"))
    )
    (comp (ref "U$3")
      (value "TXC_7Z7Q")
      (footprint "eagle-import:TCXO_3.2X2.5")
      (libsource (lib "eagle-import") (part "TXC_7Z7Q"))
    )
    (comp (ref "U$4")
      (value "JTI_ANTENNA-1575AT43A40")
      (footprint "eagle-import:JTI_ANTENNA-1575AT43A40")
      (libsource (lib "eagle-import") (part "JTI_ANTENNA-1575AT43A40"))
    )
    (comp (ref "X1")
      (value "52745-2490")
      (footprint "eagle-import:52745-2490")
      (libsource (lib "eagle-import") (part "52745-2490"))
    )
  )
  (nets
    (net (code "1") (name "BATTERY") (class "Default")
      (node (ref "BATT") (pin "+") (pinfunction "+_+") (pintype "bidirectional"))
      (node (ref "JP4") (pin "8") (pinfunction "8_8") (pintype "passive"))
      (node (ref "SJ3") (pin "1") (pinfunction "1_1") (pintype "passive"))
    )
    (net (code "2") (name "BOOT0") (class "Default")
      (node (ref "IC5") (pin "D6") (pinfunction "BOOT0_D6") (pintype "bidirectional"))
      (node (ref "SJ7") (pin "1") (pinfunction "1_1") (pintype "passive"))
    )
    (net (code "3") (name "CAM_D2") (class "Default")
      (node (ref "IC5") (pin "H15") (pinfunction "PC6_H15") (pintype "bidirectional"))
      (node (ref "X1") (pin "6") (pinfunction "S_6") (pintype "passive"))
    )
    (net (code "4") (name "CAM_D3") (class "Default")
      (node (ref "IC5") (pin "G15") (pinfunction "PC7_G15") (pintype "bidirectional"))
      (node (ref "X1") (pin "4") (pinfunction "S_4") (pintype "passive"))
    )
    (net (code "5") (name "CAM_D4") (class "Default")
      (node (ref "IC5") (pin "G14") (pinfunction "PC8_G14") (pintype "bidirectional"))
      (node (ref "X1") (pin "3") (pinfunction "S_3") (pintype "passive"))
    )
    (net (code "6") (name "CAM_D5") (class "Default")
      (node (ref "IC5") (pin "F14") (pinfunction "PC9_F14") (pintype "bidirectional"))
      (node (ref "X1") (pin "5") (pinfunction "S_5") (pintype "passive"))
    )
    (net (code "7") (name "CAM_D6") (class "Default")
      (node (ref "IC5") (pin "B1") (pinfunction "PE4_B1") (pintype "bidirectional"))
      (node (ref "X1") (pin "7") (pinfunction "S_7") (pintype "passive"))
    )
    (net (code "8") (name "CAM_D7") (class "Default")
      (node (ref "IC5") (pin "B6") (pinfunction "PB6_B6") (pintype "bidirectional"))
      (node (ref "X1") (pin "9") (pinfunction "S_9") (pintype "passive"))
    )
    (net (code "9") (name "CAM_D8") (class "Default")
      (node (ref "IC5") (pin "B2") (pinfunction "PE5_B2") (pintype "bidirectional"))
      (node (ref "X1") (pin "11") (pinfunction "S_11") (pintype "passive"))
    )
    (net (code "10") (name "CAM_D9") (class "Default")
      (node (ref "IC5") (pin "B3") (pinfunction "PE6_B3") (pintype "bidirectional"))
      (node (ref "X1") (pin "13") (pinfunction "S_13") (pintype "passive"))
    )
    (net (code "11") (name "CAM_EN") (class "Default")
      (node (ref "IC14") (pin "3") (pinfunction "SHDN*_3") (pintype "input"))
      (node (ref "IC5") (pin "A1") (pinfunction "PE3_A1") (pintype "bidirectional"))
      (node (ref "IC8") (pin "3") (pinfunction "SHDN*_3") (pintype "input"))
      (node (ref "R27") (pin "P$2") (pinfunction "2_P$2") (pintype "passive"))
    )
    (net (code "12") (name "CAM_HREF") (class "Default")
      (node (ref "IC5") (pin "N4") (pinfunction "PA4_N4") (pintype "bidirectional"))
      (node (ref "X1") (pin "16") (pinfunction "S_16") (pintype "passive"))
    )
    (net (code "13") (name "CAM_PCLK") (class "Default")
      (node (ref "C44") (pin "P$1") (pinfunction "1_P$1") (pintype "passive"))
      (node (ref "IC5") (pin "P3") (pinfunction "PA6_P3") (pintype "bidirectional"))
      (node (ref "X1") (pin "8") (pinfunction "S_8") (pintype "passive"))
    )
    (net (code "14") (name "CAM_VCC") (class "Default")
      (node (ref "C52") (pin "P$1") (pinfunction "1_P$1") (pintype "passive"))
      (node (ref "IC8") (pin "5") (pinfunction "VOUT_5") (pintype "output"))
      (node (ref "R10") (pin "P$1") (pinfunction "1_P$1") (pintype "passive"))
      (node (ref "X1") (pin "14") (pinfunction "S_14") (pintype "passive"))
      (node (ref "X1") (pin "19") (pinfunction "S_19") (pintype "passive"))
    )
    (net (code "15") (name "CAM_VCC_ANALOG") (class "Default")
      (node (ref "C42") (pin "P$1") (pinfunction "1_P$1") (pintype "passive"))
      (node (ref "C71") (pin "P$1") (pinfunction "1_P$1") (pintype "passive"))
      (node (ref "IC14") (pin "5") (pinfunction "VOUT_5") (pintype "output"))
      (node (ref "X1") (pin "21") (pinfunction "S_21") (pintype "passive"))
    )
    (net (code "16") (name "CAM_VSYNC") (class "Default")
      (node (ref "IC5") (pin "B5") (pinfunction "PB7_B5") (pintype "bidirectional"))
      (node (ref "X1") (pin "18") (pinfunction "S_18") (pintype "passive"))
    )
    (net (code "17") (name "CAM_XCLK") (class "Default")
      (node (ref "IC5") (pin "F15") (pinfunction "PA8_F15") (pintype "bidirectional"))
      (node (ref "X1") (pin "12") (pinfunction "S_12") (pintype "passive"))
    )
    (net (code "18") (name "CLOCK") (class "Default")
      (node (ref "C16") (pin "P$2") (pinfunction "2_P$2") (pintype "passive"))
      (node (ref "C17") (pin "P$2") (pinfunction "2_P$2") (pintype "passive"))
      (node (ref "C41") (pin "P$2") (pinfunction "2_P$2") (pintype "passive"))
      (node (ref "C8") (pin "P$2") (pinfunction "2_P$2") (pintype "passive"))
      (node (ref "R22") (pin "P$2") (pinfunction "2_P$2") (pintype "passive"))
      (node (ref "U$3") (pin "3") (pinfunction "OUT_3") (pintype "bidirectional"))
    )
    (net (code "19") (name "GND") (class "Default")
      (node (ref "BATT") (pin "-") (pinfunction "-_-") (pintype "bidirectional"))
      (node (ref "C10") (pin "P$1") (pinfunction "1_P$1") (pintype "passive"))
      (node (ref "C11") (pin "P$1") (pinfunction "1_P$1") (pintype "passive"))
      (node (ref "C12") (pin "P$1") (pinfunction "1_P$1") (pintype "passive"))
      (node (ref "C15") (pin "P$2") (pinfunction "2_P$2") (pintype "passive"))
      (node (ref "C18") (pin "P$1") (pinfunction "1_P$1") (pintype "passive"))
      (node (ref "C19") (pin "P$1") (pinfunction "1_P$1") (pintype "passive"))
      (node (ref "C20") (pin "P$1") (pinfunction "1_P$1") (pintype "passive"))
      (node (ref "C21") (pin "P$1") (pinfunction "1_P$1") (pintype "passive"))
      (node (ref "C22") (pin "P$1") (pinfunction "1_P$1") (pintype "passive"))
      (node (ref "C23") (pin "P$1") (pinfunction "1_P$1") (pintype "passive"))
      (node (ref "C25") (pin "P$1") (pinfunction "1_P$1") (pintype "passive"))
      (node (ref "C26") (pin "P$1") (pinfunction "1_P$1") (pintype "passive"))
      (node (ref "C27") (pin "P$2") (pinfunction "2_P$2") (pintype "passive"))
      (node (ref "C28") (pin "P$2") (pinfunction "2_P$2") (pintype "passive"))
      (node (ref "C29") (pin "P$2") (pinfunction "2_P$2") (pintype "passive"))
      (node (ref "C30") (pin "P$2") (pinfunction "2_P$2") (pintype "passive"))
      (node (ref "C31") (pin "P$2") (pinfunction "2_P$2") (pintype "passive"))
      (node (ref "C32") (pin "P$2") (pinfunction "2_P$2") (pintype "passive"))
      (node (ref "C33") (pin "P$2") (pinfunction "2_P$2") (pintype "passive"))
      (node (ref "C34") (pin "P$2") (pinfunction "2_P$2") (pintype "passive"))
      (node (ref "C35") (pin "P$2") (pinfunction "2_P$2") (pintype "passive"))
      (node (ref "C36") (pin "P$2") (pinfunction "2_P$2") (pintype "passive"))
      (node (ref "C37") (pin "1") (pinfunction "1_1") (pintype "passive"))
      (node (ref "C38") (pin "P$2") (pinfunction "2_P$2") (pintype "passive"))
      (node (ref "C39") (pin "1") (pinfunction "1_1") (pintype "passive"))
      (node (ref "C4") (pin "P$1") (pinfunction "1_P$1") (pintype "passive"))
      (node (ref "C40") (pin "P$1") (pinfunction "1_P$1") (pintype "passive"))
      (node (ref "C42") (pin "P$2") (pinfunction "2_P$2") (pintype "passive"))
      (node (ref "C43") (pin "P$2") (pinfunction "2_P$2") (pintype "passive"))
      (node (ref "C44") (pin "P$2") (pinfunction "2_P$2") (pintype "passive"))
      (node (ref "C45") (pin "P$1") (pinfunction "1_P$1") (pintype "passive"))
      (node (ref "C46") (pin "1") (pinfunction "1_1") (pintype "passive"))
      (node (ref "C47") (pin "1") (pinfunction "1_1") (pintype "passive"))
      (node (ref "C48") (pin "P$2") (pinfunction "2_P$2") (pintype "passive"))
      (node (ref "C49") (pin "1") (pinfunction "1_1") (pintype "passive"))
      (node (ref "C5") (pin "P$1") (pinfunction "1_P$1") (pintype "passive"))
      (node (ref "C50") (pin "1") (pinfunction "1_1") (pintype "passive"))
      (node (ref "C52") (pin "P$2") (pinfunction "2_P$2") (pintype "passive"))
      (node (ref "C53") (pin "P$2") (pinfunction "2_P$2") (pintype "passive"))
      (node (ref "C55") (pin "P$1") (pinfunction "1_P$1") (pintype "passive"))
      (node (ref "C57") (pin "P$2") (pinfunction "2_P$2") (pintype "passive"))
      (node (ref "C59") (pin "P$1") (pinfunction "1_P$1") (pintype "passive"))
      (node (ref "C6") (pin "P$1") (pinfunction "1_P$1") (pintype "passive"))
      (node (ref "C60") (pin "P$1") (pinfunction "1_P$1") (pintype "passive"))
      (node (ref "C61") (pin "P$1") (pinfunction "1_P$1") (pintype "passive"))
      (node (ref "C62") (pin "1") (pinfunction "1_1") (pintype "passive"))
      (node (ref "C65") (pin "P$1") (pinfunction "1_P$1") (pintype "passive"))
      (node (ref "C66") (pin "P$1") (pinfunction "1_P$1") (pintype "passive"))
      (node (ref "C67") (pin "P$1") (pinfunction "1_P$1") (pintype "passive"))
      (node (ref "C68") (pin "P$1") (pinfunction "1_P$1") (pintype "passive"))
      (node (ref "C69") (pin "P$1") (pinfunction "1_P$1") (pintype "passive"))
      (node (ref "C7") (pin "1") (pinfunction "1_1") (pintype "passive"))
      (node (ref "C71") (pin "P$2") (pinfunction "2_P$2") (pintype "passive"))
      (node (ref "C72") (pin "1") (pinfunction "1_1") (pintype "passive"))
      (node (ref "C73") (pin "1") (pinfunction "1_1") (pintype "passive"))
      (node (ref "C74") (pin "P$1") (pinfunction "1_P$1") (pintype "passive"))
      (node (ref "C75") (pin "P$1") (pinfunction "1_P$1") (pintype "passive"))
      (node (ref "C76") (pin "P$1") (pinfunction "1_P$1") (pintype "passive"))
      (node (ref "C79") (pin "P$1") (pinfunction "1_P$1") (pintype "passive"))
      (node (ref "C80") (pin "P$2") (pinfunction "2_P$2") (pintype "passive"))
      (node (ref "C81") (pin "P$2") (pinfunction "2_P$2") (pintype "passive"))
      (node (ref "C82") (pin "P$2") (pinfunction "2_P$2") (pintype "passive"))
      (node (ref "C9") (pin "P$1") (pinfunction "1_P$1") (pintype "passive"))
      (node (ref "IC1") (pin "18") (pinfunction "GNDX_18") (pintype "bidirectional"))
      (node (ref "IC1") (pin "21") (pinfunction "GND_21") (pintype "bidirectional"))
      (node (ref "IC1") (pin "22") (pinfunction "GND_22") (pintype "bidirectional"))
      (node (ref "IC1") (pin "23") (pinfunction "GND_23") (pintype "bidirectional"))
      (node (ref "IC1") (pin "24") (pinfunction "GND_24") (pintype "bidirectional"))
      (node (ref "IC1") (pin "25") (pinfunction "GND_25") (pintype "bidirectional"))
      (node (ref "IC1") (pin "5") (pinfunction "NC_5") (pintype "bidirectional"))
      (node (ref "IC10") (pin "2") (pinfunction "MODE_2") (pintype "input"))
      (node (ref "IC10") (pin "6") (pinfunction "GND_6") (pintype "passive"))
      (node (ref "IC10") (pin "7") (pinfunction "THERMALPAD_7") (pintype "passive"))
      (node (ref "IC11") (pin "2") (pinfunction "MODE_2") (pintype "input"))
      (node (ref "IC11") (pin "6") (pinfunction "GND_6") (pintype "passive"))
      (node (ref "IC11") (pin "7") (pinfunction "THERMALPAD_7") (pintype "passive"))
      (node (ref "IC12") (pin "2") (pinfunction "GND_2") (pintype "bidirectional"))
      (node (ref "IC12") (pin "PGND1") (pinfunction "PGND_PGND1") (pintype "bidirectional"))
      (node (ref "IC12") (pin "PGND10") (pinfunction "PGND_PGND10") (pintype "bidirectional"))
      (node (ref "IC12") (pin "PGND11") (pinfunction "PGND_PGND11") (pintype "bidirectional"))
      (node (ref "IC12") (pin "PGND12") (pinfunction "PGND_PGND12") (pintype "bidirectional"))
      (node (ref "IC12") (pin "PGND2") (pinfunction "PGND_PGND2") (pintype "bidirectional"))
      (node (ref "IC12") (pin "PGND3") (pinfunction "PGND_PGND3") (pintype "bidirectional"))
      (node (ref "IC12") (pin "PGND4") (pinfunction "PGND_PGND4") (pintype "bidirectional"))
      (node (ref "IC12") (pin "PGND5") (pinfunction "PGND_PGND5") (pintype "bidirectional"))
      (node (ref "IC12") (pin "PGND6") (pinfunction "PGND_PGND6") (pintype "bidirectional"))
      (node (ref "IC12") (pin "PGND7") (pinfunction "PGND_PGND7") (pintype "bidirectional"))
      (node (ref "IC12") (pin "PGND8") (pinfunction "PGND_PGND8") (pintype "bidirectional"))
      (node (ref "IC12") (pin "PGND9") (pinfunction "PGND_PGND9") (pintype "bidirectional"))
      (node (ref "IC13") (pin "25") (pinfunction "GND_25") (pintype "bidirectional"))
      (node (ref "IC13") (pin "GND") (pinfunction "GND_GND") (pintype "bidirectional"))
      (node (ref "IC13") (pin "P$26") (pinfunction "GND_P$26") (pintype "bidirectional"))
      (node (ref "IC13") (pin "P$27") (pinfunction "GND_P$27") (pintype "bidirectional"))
      (node (ref "IC13") (pin "P$28") (pinfunction "GND_P$28") (pintype "bidirectional"))
      (node (ref "IC13") (pin "P$29") (pinfunction "GND_P$29") (pintype "bidirectional"))
      (node (ref "IC14") (pin "2") (pinfunction "GND_2") (pintype "passive"))
      (node (ref "IC16") (pin "11") (pinfunction "EP_11") (pintype "power_in"))
      (node (ref "IC16") (pin "5") (pinfunction "GND_5") (pintype "power_in"))
      (node (ref "IC16") (pin "6") (pinfunction "ADDR_SEL_6") (pintype "input"))
      (node (ref "IC2") (pin "18") (pinfunction "GNDX_18") (pintype "bidirectional"))
      (node (ref "IC2") (pin "21") (pinfunction "GND_21") (pintype "bidirectional"))
      (node (ref "IC2") (pin "22") (pinfunction "GND_22") (pintype "bidirectional"))
      (node (ref "IC2") (pin "23") (pinfunction "GND_23") (pintype "bidirectional"))
      (node (ref "IC2") (pin "24") (pinfunction "GND_24") (pintype "bidirectional"))
      (node (ref "IC2") (pin "25") (pinfunction "GND_25") (pintype "bidirectional"))
      (node (ref "IC2") (pin "5") (pinfunction "NC_5") (pintype "bidirectional"))
      (node (ref "IC3") (pin "1") (pinfunction "GND1_1") (pintype "bidirectional"))
      (node (ref "IC3") (pin "7") (pinfunction "GND2_7") (pintype "bidirectional"))
      (node (ref "IC4") (pin "10_GND") (pinfunction "10_GND_10_GND") (pintype "power_in"))
      (node (ref "IC4") (pin "12_GND") (pinfunction "12_GND_12_GND") (pintype "power_in"))
      (node (ref "IC4") (pin "1_GND") (pinfunction "1_GND_1_GND") (pintype "power_in"))
      (node (ref "IC5") (pin "D5") (pinfunction "VSS1_D5") (pintype "bidirectional"))
      (node (ref "IC5") (pin "D7") (pinfunction "VSS2_D7") (pintype "bidirectional"))
      (node (ref "IC5") (pin "D8") (pinfunction "VSS3_D8") (pintype "bidirectional"))
      (node (ref "IC5") (pin "D9") (pinfunction "VSS4_D9") (pintype "bidirectional"))
      (node (ref "IC5") (pin "F10") (pinfunction "VSS10_F10") (pintype "bidirectional"))
      (node (ref "IC5") (pin "F12") (pinfunction "VSS11_F12") (pintype "bidirectional"))
      (node (ref "IC5") (pin "F2") (pinfunction "VSS5_F2") (pintype "bidirectional"))
      (node (ref "IC5") (pin "F6") (pinfunction "VSS6_F6") (pintype "bidirectional"))
      (node (ref "IC5") (pin "F7") (pinfunction "VSS7_F7") (pintype "bidirectional"))
      (node (ref "IC5") (pin "F8") (pinfunction "VSS8_F8") (pintype "bidirectional"))
      (node (ref "IC5") (pin "F9") (pinfunction "VSS9_F9") (pintype "bidirectional"))
      (node (ref "IC5") (pin "G10") (pinfunction "VSS17_G10") (pintype "bidirectional"))
      (node (ref "IC5") (pin "G12") (pinfunction "VSS18_G12") (pintype "bidirectional"))
      (node (ref "IC5") (pin "G2") (pinfunction "VSS12_G2") (pintype "bidirectional"))
      (node (ref "IC5") (pin "G6") (pinfunction "VSS13_G6") (pintype "bidirectional"))
      (node (ref "IC5") (pin "G7") (pinfunction "VSS14_G7") (pintype "bidirectional"))
      (node (ref "IC5") (pin "G8") (pinfunction "VSS15_G8") (pintype "bidirectional"))
      (node (ref "IC5") (pin "G9") (pinfunction "VSS16_G9") (pintype "bidirectional"))
      (node (ref "IC5") (pin "H10") (pinfunction "VSS23_H10") (pintype "bidirectional"))
      (node (ref "IC5") (pin "H12") (pinfunction "VSS24_H12") (pintype "bidirectional"))
      (node (ref "IC5") (pin "H6") (pinfunction "VSS19_H6") (pintype "bidirectional"))
      (node (ref "IC5") (pin "H7") (pinfunction "VSS20_H7") (pintype "bidirectional"))
      (node (ref "IC5") (pin "H8") (pinfunction "VSS21_H8") (pintype "bidirectional"))
      (node (ref "IC5") (pin "H9") (pinfunction "VSS22_H9") (pintype "bidirectional"))
      (node (ref "IC5") (pin "J10") (pinfunction "VSS29_J10") (pintype "bidirectional"))
      (node (ref "IC5") (pin "J6") (pinfunction "VSS25_J6") (pintype "bidirectional"))
      (node (ref "IC5") (pin "J7") (pinfunction "VSS26_J7") (pintype "bidirectional"))
      (node (ref "IC5") (pin "J8") (pinfunction "VSS27_J8") (pintype "bidirectional"))
      (node (ref "IC5") (pin "J9") (pinfunction "VSS28_J9") (pintype "bidirectional"))
      (node (ref "IC5") (pin "K10") (pinfunction "VSS34_K10") (pintype "bidirectional"))
      (node (ref "IC5") (pin "K6") (pinfunction "VSS30_K6") (pintype "bidirectional"))
      (node (ref "IC5") (pin "K7") (pinfunction "VSS31_K7") (pintype "bidirectional"))
      (node (ref "IC5") (pin "K8") (pinfunction "VSS32_K8") (pintype "bidirectional"))
      (node (ref "IC5") (pin "K9") (pinfunction "VSS33_K9") (pintype "bidirectional"))
      (node (ref "IC5") (pin "L4") (pinfunction "BYPASS_REG_L4") (pintype "bidirectional"))
      (node (ref "IC5") (pin "M1") (pinfunction "VSSA_M1") (pintype "bidirectional"))
      (node (ref "IC5") (pin "M8") (pinfunction "VSS35_M8") (pintype "bidirectional"))
      (node (ref "IC5") (pin "M9") (pinfunction "VSS36_M9") (pintype "bidirectional"))
      (node (ref "IC5") (pin "N1") (pinfunction "VREF-_N1") (pintype "bidirectional"))
      (node (ref "IC6") (pin "2") (pinfunction "GND1_2") (pintype "bidirectional"))
      (node (ref "IC6") (pin "3") (pinfunction "GND2_3") (pintype "bidirectional"))
      (node (ref "IC6") (pin "4") (pinfunction "GND3_4") (pintype "bidirectional"))
      (node (ref "IC6") (pin "9") (pinfunction "GND4_9") (pintype "bidirectional"))
      (node (ref "IC7") (pin "2") (pinfunction "GND_2") (pintype "bidirectional"))
      (node (ref "IC8") (pin "2") (pinfunction "GND_2") (pintype "passive"))
      (node (ref "IC9") (pin "2") (pinfunction "GND_2") (pintype "passive"))
      (node (ref "J$1") (pin "GND@0") (pinfunction "GND_GND@0") (pintype "bidirectional"))
      (node (ref "J$1") (pin "GND@1") (pinfunction "GND_GND@1") (pintype "bidirectional"))
      (node (ref "J$1") (pin "GND@2") (pinfunction "GND_GND@2") (pintype "bidirectional"))
      (node (ref "J$1") (pin "GND@3") (pinfunction "GND_GND@3") (pintype "bidirectional"))
      (node (ref "J$2") (pin "GND@0") (pinfunction "GND_GND@0") (pintype "bidirectional"))
      (node (ref "J$2") (pin "GND@1") (pinfunction "GND_GND@1") (pintype "bidirectional"))
      (node (ref "J$2") (pin "GND@2") (pinfunction "GND_GND@2") (pintype "bidirectional"))
      (node (ref "J$2") (pin "GND@3") (pinfunction "GND_GND@3") (pintype "bidirectional"))
      (node (ref "JP3") (pin "12") (pinfunction "12_12") (pintype "passive"))
      (node (ref "JP3") (pin "3") (pinfunction "3_3") (pintype "passive"))
      (node (ref "JP3") (pin "9") (pinfunction "9_9") (pintype "passive"))
      (node (ref "JP4") (pin "3") (pinfunction "3_3") (pintype "passive"))
      (node (ref "JP4") (pin "4") (pinfunction "4_4") (pintype "passive"))
      (node (ref "JP5") (pin "P$1") (pinfunction "1_P$1") (pintype "passive"))
      (node (ref "JP6") (pin "P$1") (pinfunction "1_P$1") (pintype "passive"))
      (node (ref "L12") (pin "P$1") (pinfunction "1_P$1") (pintype "passive"))
      (node (ref "L17") (pin "P$1") (pinfunction "1_P$1") (pintype "passive"))
      (node (ref "L20") (pin "P$1") (pinfunction "1_P$1") (pintype "passive"))
      (node (ref "LED1") (pin "C") (pinfunction "C_C") (pintype "passive"))
      (node (ref "LED2") (pin "C") (pinfunction "C_C") (pintype "passive"))
      (node (ref "LED3") (pin "C") (pinfunction "C_C") (pintype "passive"))
      (node (ref "LED4") (pin "C") (pinfunction "C_C") (pintype "passive"))
      (node (ref "R14") (pin "P$1") (pinfunction "1_P$1") (pintype "passive"))
      (node (ref "R16") (pin "P$1") (pinfunction "1_P$1") (pintype "passive"))
      (node (ref "R18") (pin "P$1") (pinfunction "1_P$1") (pintype "passive"))
      (node (ref "R19") (pin "P$1") (pinfunction "1_P$1") (pintype "passive"))
      (node (ref "R25") (pin "P$1") (pinfunction "1_P$1") (pintype "passive"))
      (node (ref "R26") (pin "P$1") (pinfunction "1_P$1") (pintype "passive"))
      (node (ref "R27") (pin "P$1") (pinfunction "1_P$1") (pintype "passive"))
      (node (ref "R30") (pin "P$1") (pinfunction "1_P$1") (pintype "passive"))
      (node (ref "R37") (pin "P$1") (pinfunction "1_P$1") (pintype "passive"))
      (node (ref "SJ7") (pin "2") (pinfunction "2_2") (pintype "passive"))
      (node (ref "U$1") (pin "1") (pinfunction "NC_1") (pintype "bidirectional"))
      (node (ref "U$1") (pin "6") (pinfunction "VSS_6") (pintype "bidirectional"))
      (node (ref "U$2") (pin "2") (pinfunction "GND_2") (pintype "bidirectional"))
      (node (ref "U$3") (pin "1") (pinfunction "AFC_1") (pintype "bidirectional"))
      (node (ref "U$3") (pin "2") (pinfunction "GND_2") (pintype "bidirectional"))
      (node (ref "X1") (pin "10") (pinfunction "S_10") (pintype "passive"))
      (node (ref "X1") (pin "17") (pinfunction "S_17") (pintype "passive"))
      (node (ref "X1") (pin "23") (pinfunction "S_23") (pintype "passive"))
      (node (ref "X1") (pin "P$1") (pinfunction "S_P$1") (pintype "passive"))
      (node (ref "X1") (pin "P$2") (pinfunction "S_P$2") (pintype "passive"))
      (node (ref "X1") (pin "P$3") (pinfunction "S_P$3") (pintype "passive"))
      (node (ref "X1") (pin "P$4") (pinfunction "S_P$4") (pintype "passive"))
    )
    (net (code "20") (name "GPS_BIAS") (class "Default")
      (node (ref "C76") (pin "P$2") (pinfunction "2_P$2") (pintype "passive"))
      (node (ref "R35") (pin "P$2") (pinfunction "2_P$2") (pintype "passive"))
      (node (ref "SJ1") (pin "2") (pinfunction "2_2") (pintype "passive"))
    )
    (net (code "21") (name "GPS_EN") (class "Default")
      (node (ref "IC10") (pin "4") (pinfunction "EN_4") (pintype "input"))
      (node (ref "IC5") (pin "P2") (pinfunction "PA2_P2") (pintype "bidirectional"))
      (node (ref "R26") (pin "P$2") (pinfunction "2_P$2") (pintype "passive"))
    )
    (net (code "22") (name "GPS_RESET") (class "Default")
      (node (ref "IC4") (pin "9_V_RESET") (pinfunction "9_V_RESET_9_V_RESET") (pintype "power_in"))
      (node (ref "IC5") (pin "R5") (pinfunction "PB0_R5") (pintype "bidirectional"))
      (node (ref "R9") (pin "P$2") (pinfunction "2_P$2") (pintype "passive"))
    )
    (net (code "23") (name "I2C_SCL") (class "Default")
      (node (ref "IC16") (pin "9") (pinfunction "SMCLK_9") (pintype "passive"))
      (node (ref "IC3") (pin "4") (pinfunction "SCK_4") (pintype "bidirectional"))
      (node (ref "IC4") (pin "17_SCL2") (pinfunction "17_SCL2_17_SCL2") (pintype "bidirectional"))
      (node (ref "IC5") (pin "R12") (pinfunction "PB10_R12") (pintype "bidirectional"))
      (node (ref "JP4") (pin "5") (pinfunction "5_5") (pintype "passive"))
      (node (ref "R8") (pin "P$1") (pinfunction "1_P$1") (pintype "passive"))
      (node (ref "X1") (pin "20") (pinfunction "S_20") (pintype "passive"))
    )
    (net (code "24") (name "I2C_SDA") (class "Default")
      (node (ref "IC16") (pin "8") (pinfunction "SMDATA_8") (pintype "passive"))
      (node (ref "IC3") (pin "3") (pinfunction "SDI_3") (pintype "bidirectional"))
      (node (ref "IC4") (pin "16_SDA2") (pinfunction "16_SDA2_16_SDA2") (pintype "bidirectional"))
      (node (ref "IC5") (pin "R13") (pinfunction "PB11_R13") (pintype "bidirectional"))
      (node (ref "JP4") (pin "7") (pinfunction "7_7") (pintype "passive"))
      (node (ref "R7") (pin "P$1") (pinfunction "1_P$1") (pintype "passive"))
      (node (ref "X1") (pin "22") (pinfunction "S_22") (pintype "passive"))
    )
    (net (code "25") (name "LED1") (class "Default")
      (node (ref "IC5") (pin "H1") (pinfunction "PH1_H1") (pintype "bidirectional"))
      (node (ref "JP3") (pin "8") (pinfunction "8_8") (pintype "passive"))
      (node (ref "R31") (pin "P$2") (pinfunction "2_P$2") (pintype "passive"))
    )
    (net (code "26") (name "LED2") (class "Default")
      (node (ref "IC5") (pin "D2") (pinfunction "PI8_D2") (pintype "bidirectional"))
      (node (ref "JP3") (pin "7") (pinfunction "7_7") (pintype "passive"))
      (node (ref "R32") (pin "P$2") (pinfunction "2_P$2") (pintype "passive"))
    )
    (net (code "27") (name "LED3") (class "Default")
      (node (ref "IC5") (pin "D1") (pinfunction "PC13_D1") (pintype "bidirectional"))
      (node (ref "R33") (pin "P$2") (pinfunction "2_P$2") (pintype "passive"))
    )
    (net (code "28") (name "LED4") (class "Default")
      (node (ref "IC5") (pin "K1") (pinfunction "PF7_K1") (pintype "bidirectional"))
      (node (ref "R34") (pin "P$2") (pinfunction "2_P$2") (pintype "passive"))
    )
    (net (code "29") (name "NRST") (class "Default")
      (node (ref "IC5") (pin "J1") (pinfunction "NRST_J1") (pintype "bidirectional"))
      (node (ref "JP3") (pin "5") (pinfunction "5_5") (pintype "passive"))
    )
    (net (code "30") (name "Net-(C1-1)") (class "Default")
      (node (ref "C1") (pin "P$1") (pinfunction "1_P$1") (pintype "passive"))
      (node (ref "C12") (pin "P$2") (pinfunction "2_P$2") (pintype "passive"))
      (node (ref "C24") (pin "P$1") (pinfunction "1_P$1") (pintype "passive"))
      (node (ref "L6") (pin "P$2") (pinfunction "2_P$2") (pintype "passive"))
    )
    (net (code "31") (name "Net-(C1-2)") (class "Default")
      (node (ref "C1") (pin "P$2") (pinfunction "2_P$2") (pintype "passive"))
      (node (ref "IC13") (pin "6") (pinfunction "RF_IN_6") (pintype "bidirectional"))
    )
    (net (code "32") (name "Net-(C2-2)") (class "Default")
      (node (ref "C2") (pin "P$2") (pinfunction "2_P$2") (pintype "passive"))
      (node (ref "C51") (pin "P$2") (pinfunction "2_P$2") (pintype "passive"))
      (node (ref "C59") (pin "P$2") (pinfunction "2_P$2") (pintype "passive"))
      (node (ref "L1") (pin "P$1") (pinfunction "1_P$1") (pintype "passive"))
    )
    (net (code "33") (name "Net-(C3-1)") (class "Default")
      (node (ref "C3") (pin "P$1") (pinfunction "1_P$1") (pintype "passive"))
      (node (ref "L3") (pin "P$1") (pinfunction "1_P$1") (pintype "passive"))
    )
    (net (code "34") (name "Net-(C3-2)") (class "Default")
      (node (ref "C3") (pin "P$2") (pinfunction "2_P$2") (pintype "passive"))
      (node (ref "IC1") (pin "4") (pinfunction "TX_4") (pintype "bidirectional"))
      (node (ref "L5") (pin "P$1") (pinfunction "1_P$1") (pintype "passive"))
    )
    (net (code "35") (name "Net-(C8-1)") (class "Default")
      (node (ref "C8") (pin "P$1") (pinfunction "1_P$1") (pintype "passive"))
      (node (ref "IC1") (pin "17") (pinfunction "XIN_17") (pintype "bidirectional"))
    )
    (net (code "36") (name "Net-(C13-1)") (class "Default")
      (node (ref "C13") (pin "P$1") (pinfunction "1_P$1") (pintype "passive"))
      (node (ref "L7") (pin "P$1") (pinfunction "1_P$1") (pintype "passive"))
    )
    (net (code "37") (name "Net-(C13-2)") (class "Default")
      (node (ref "C13") (pin "P$2") (pinfunction "2_P$2") (pintype "passive"))
      (node (ref "IC2") (pin "4") (pinfunction "TX_4") (pintype "bidirectional"))
      (node (ref "L8") (pin "P$1") (pinfunction "1_P$1") (pintype "passive"))
    )
    (net (code "38") (name "Net-(C14-1)") (class "Default")
      (node (ref "C14") (pin "P$1") (pinfunction "1_P$1") (pintype "passive"))
      (node (ref "C58") (pin "P$1") (pinfunction "1_P$1") (pintype "passive"))
      (node (ref "C60") (pin "P$2") (pinfunction "2_P$2") (pintype "passive"))
      (node (ref "J$1") (pin "SIG") (pinfunction "SIGNAL_SIG") (pintype "bidirectional"))
      (node (ref "L4") (pin "P$2") (pinfunction "2_P$2") (pintype "passive"))
      (node (ref "R39") (pin "P$2") (pinfunction "2_P$2") (pintype "passive"))
    )
    (net (code "39") (name "Net-(C14-2)") (class "Default")
      (node (ref "C14") (pin "P$2") (pinfunction "2_P$2") (pintype "passive"))
      (node (ref "C2") (pin "P$1") (pinfunction "1_P$1") (pintype "passive"))
      (node (ref "C58") (pin "P$2") (pinfunction "2_P$2") (pintype "passive"))
      (node (ref "C6") (pin "P$2") (pinfunction "2_P$2") (pintype "passive"))
      (node (ref "L1") (pin "P$2") (pinfunction "2_P$2") (pintype "passive"))
      (node (ref "L4") (pin "P$1") (pinfunction "1_P$1") (pintype "passive"))
    )
    (net (code "40") (name "Net-(C16-1)") (class "Default")
      (node (ref "C16") (pin "P$1") (pinfunction "1_P$1") (pintype "passive"))
      (node (ref "IC2") (pin "17") (pinfunction "XIN_17") (pintype "bidirectional"))
    )
    (net (code "41") (name "Net-(C17-1)") (class "Default")
      (node (ref "C17") (pin "P$1") (pinfunction "1_P$1") (pintype "passive"))
      (node (ref "IC1") (pin "16") (pinfunction "XOUT_16") (pintype "bidirectional"))
    )
    (net (code "42") (name "Net-(C21-2)") (class "Default")
      (node (ref "C21") (pin "P$2") (pinfunction "2_P$2") (pintype "passive"))
      (node (ref "L19") (pin "P$1") (pinfunction "1_P$1") (pintype "passive"))
      (node (ref "L9") (pin "P$2") (pinfunction "2_P$2") (pintype "passive"))
    )
    (net (code "43") (name "Net-(C22-2)") (class "Default")
      (node (ref "C22") (pin "P$2") (pinfunction "2_P$2") (pintype "passive"))
      (node (ref "IC2") (pin "2") (pinfunction "RXP_2") (pintype "bidirectional"))
      (node (ref "L10") (pin "P$2") (pinfunction "2_P$2") (pintype "passive"))
    )
    (net (code "44") (name "Net-(C24-2)") (class "Default")
      (node (ref "C24") (pin "P$2") (pinfunction "2_P$2") (pintype "passive"))
      (node (ref "C4") (pin "P$2") (pinfunction "2_P$2") (pintype "passive"))
      (node (ref "L3") (pin "P$2") (pinfunction "2_P$2") (pintype "passive"))
      (node (ref "L6") (pin "P$1") (pinfunction "1_P$1") (pintype "passive"))
    )
    (net (code "45") (name "Net-(C26-2)") (class "Default")
      (node (ref "C26") (pin "P$2") (pinfunction "2_P$2") (pintype "passive"))
      (node (ref "IC4") (pin "8_VCC") (pinfunction "8_VCC_8_VCC") (pintype "power_in"))
      (node (ref "L15") (pin "P$2") (pinfunction "2_P$2") (pintype "passive"))
      (node (ref "R36") (pin "P$2") (pinfunction "2_P$2") (pintype "passive"))
      (node (ref "SJ2") (pin "2") (pinfunction "2_2") (pintype "passive"))
    )
    (net (code "46") (name "Net-(C27-1)") (class "Default")
      (node (ref "C27") (pin "P$1") (pinfunction "1_P$1") (pintype "passive"))
      (node (ref "IC5") (pin "F13") (pinfunction "VCAP2_F13") (pintype "bidirectional"))
    )
    (net (code "47") (name "Net-(C28-1)") (class "Default")
      (node (ref "C28") (pin "P$1") (pinfunction "1_P$1") (pintype "passive"))
      (node (ref "IC5") (pin "M10") (pinfunction "VCAP1_M10") (pintype "bidirectional"))
    )
    (net (code "48") (name "Net-(C40-2)") (class "Default")
      (node (ref "C40") (pin "P$2") (pinfunction "2_P$2") (pintype "passive"))
      (node (ref "J$2") (pin "SIG") (pinfunction "SIGNAL_SIG") (pintype "bidirectional"))
      (node (ref "L19") (pin "P$2") (pinfunction "2_P$2") (pintype "passive"))
      (node (ref "R40") (pin "P$2") (pinfunction "2_P$2") (pintype "passive"))
    )
    (net (code "49") (name "Net-(C41-1)") (class "Default")
      (node (ref "C41") (pin "P$1") (pinfunction "1_P$1") (pintype "passive"))
      (node (ref "IC2") (pin "16") (pinfunction "XOUT_16") (pintype "bidirectional"))
    )
    (net (code "50") (name "Net-(C43-1)") (class "Default")
      (node (ref "C43") (pin "P$1") (pinfunction "1_P$1") (pintype "passive"))
      (node (ref "R10") (pin "P$2") (pinfunction "2_P$2") (pintype "passive"))
      (node (ref "X1") (pin "15") (pinfunction "S_15") (pintype "passive"))
    )
    (net (code "51") (name "Net-(C45-2)") (class "Default")
      (node (ref "C45") (pin "P$2") (pinfunction "2_P$2") (pintype "passive"))
      (node (ref "IC7") (pin "5") (pinfunction "VCTRL_5") (pintype "bidirectional"))
      (node (ref "R13") (pin "P$1") (pinfunction "1_P$1") (pintype "passive"))
      (node (ref "R14") (pin "P$2") (pinfunction "2_P$2") (pintype "passive"))
    )
    (net (code "52") (name "Net-(C51-1)") (class "Default")
      (node (ref "C51") (pin "P$1") (pinfunction "1_P$1") (pintype "passive"))
      (node (ref "C63") (pin "P$2") (pinfunction "2_P$2") (pintype "passive"))
      (node (ref "IC13") (pin "13") (pinfunction "RF_OUT1_13") (pintype "bidirectional"))
      (node (ref "IC13") (pin "14") (pinfunction "RF_OUT2_14") (pintype "bidirectional"))
      (node (ref "IC13") (pin "15") (pinfunction "RF_OUT3_15") (pintype "bidirectional"))
      (node (ref "IC13") (pin "16") (pinfunction "RF_OUT4_16") (pintype "bidirectional"))
      (node (ref "IC13") (pin "17") (pinfunction "RF_OUT5_17") (pintype "bidirectional"))
      (node (ref "IC13") (pin "18") (pinfunction "RF_OUT6_18") (pintype "bidirectional"))
      (node (ref "L11") (pin "P$1") (pinfunction "1_P$1") (pintype "passive"))
    )
    (net (code "53") (name "Net-(C54-1)") (class "Default")
      (node (ref "C54") (pin "P$1") (pinfunction "1_P$1") (pintype "passive"))
      (node (ref "C57") (pin "P$1") (pinfunction "1_P$1") (pintype "passive"))
      (node (ref "L9") (pin "P$1") (pinfunction "1_P$1") (pintype "passive"))
    )
    (net (code "54") (name "Net-(C54-2)") (class "Default")
      (node (ref "C54") (pin "P$2") (pinfunction "2_P$2") (pintype "passive"))
      (node (ref "U$2") (pin "5") (pinfunction "A1_5") (pintype "bidirectional"))
    )
    (net (code "55") (name "Net-(C55-2)") (class "Default")
      (node (ref "C55") (pin "P$2") (pinfunction "2_P$2") (pintype "passive"))
      (node (ref "IC12") (pin "1") (pinfunction "VINA_1") (pintype "bidirectional"))
      (node (ref "IC12") (pin "13") (pinfunction "PS_13") (pintype "bidirectional"))
    )
    (net (code "56") (name "Net-(C56-1)") (class "Default")
      (node (ref "C56") (pin "P$1") (pinfunction "1_P$1") (pintype "passive"))
      (node (ref "IC10") (pin "3") (pinfunction "FB_3") (pintype "input"))
      (node (ref "R17") (pin "P$1") (pinfunction "1_P$1") (pintype "passive"))
      (node (ref "R18") (pin "P$2") (pinfunction "2_P$2") (pintype "passive"))
    )
    (net (code "57") (name "Net-(C63-1)") (class "Default")
      (node (ref "C63") (pin "P$1") (pinfunction "1_P$1") (pintype "passive"))
      (node (ref "C64") (pin "P$2") (pinfunction "2_P$2") (pintype "passive"))
      (node (ref "L17") (pin "P$2") (pinfunction "2_P$2") (pintype "passive"))
    )
    (net (code "58") (name "Net-(C64-1)") (class "Default")
      (node (ref "C64") (pin "P$1") (pinfunction "1_P$1") (pintype "passive"))
      (node (ref "R37") (pin "P$2") (pinfunction "2_P$2") (pintype "passive"))
    )
    (net (code "59") (name "Net-(C70-1)") (class "Default")
      (node (ref "C70") (pin "P$1") (pinfunction "1_P$1") (pintype "passive"))
      (node (ref "U$2") (pin "3") (pinfunction "B1_3") (pintype "bidirectional"))
    )
    (net (code "60") (name "Net-(C70-2)") (class "Default")
      (node (ref "C70") (pin "P$2") (pinfunction "2_P$2") (pintype "passive"))
      (node (ref "IC2") (pin "3") (pinfunction "RXN_3") (pintype "bidirectional"))
      (node (ref "L10") (pin "P$1") (pinfunction "1_P$1") (pintype "passive"))
    )
    (net (code "61") (name "Net-(C74-2)") (class "Default")
      (node (ref "C74") (pin "P$2") (pinfunction "2_P$2") (pintype "passive"))
      (node (ref "C75") (pin "P$2") (pinfunction "2_P$2") (pintype "passive"))
      (node (ref "L15") (pin "P$1") (pinfunction "1_P$1") (pintype "passive"))
      (node (ref "L2") (pin "P$2") (pinfunction "2_P$2") (pintype "passive"))
      (node (ref "R36") (pin "P$1") (pinfunction "1_P$1") (pintype "passive"))
    )
    (net (code "62") (name "Net-(IC1-GPIO_2)") (class "Default")
      (node (ref "IC1") (pin "19") (pinfunction "GPIO_2_19") (pintype "bidirectional"))
      (node (ref "R2") (pin "P$2") (pinfunction "2_P$2") (pintype "passive"))
    )
    (net (code "63") (name "Net-(IC4-Pad14_VCC_RF)") (class "Default")
      (node (ref "IC4") (pin "14_VCC_RF") (pinfunction "14_VCC_RF_14_VCC_RF") (pintype "bidirectional"))
      (node (ref "SJ1") (pin "3") (pinfunction "3_3") (pintype "passive"))
    )
    (net (code "64") (name "Net-(IC5B-PH0)") (class "Default")
      (node (ref "IC5") (pin "G1") (pinfunction "PH0_G1") (pintype "bidirectional"))
      (node (ref "R22") (pin "P$1") (pinfunction "1_P$1") (pintype "passive"))
    )
    (net (code "65") (name "Net-(IC6-RF_IN)") (class "Default")
      (node (ref "IC6") (pin "1") (pinfunction "RF_IN_1") (pintype "bidirectional"))
      (node (ref "U$4") (pin "FEED") (pinfunction "FEED_FEED") (pintype "bidirectional"))
    )
    (net (code "66") (name "Net-(IC6-RF_OUT)") (class "Default")
      (node (ref "IC4") (pin "11_RF_IN") (pinfunction "11_RF_IN_11_RF_IN") (pintype "bidirectional"))
      (node (ref "IC6") (pin "6") (pinfunction "RF_OUT_6") (pintype "bidirectional"))
    )
    (net (code "67") (name "Net-(IC6-VDD)") (class "Default")
      (node (ref "IC6") (pin "7") (pinfunction "VDD_7") (pintype "bidirectional"))
      (node (ref "L2") (pin "P$1") (pinfunction "1_P$1") (pintype "passive"))
    )
    (net (code "68") (name "Net-(IC6-VSD)") (class "Default")
      (node (ref "IC6") (pin "8") (pinfunction "VSD_8") (pintype "bidirectional"))
      (node (ref "R35") (pin "P$1") (pinfunction "1_P$1") (pintype "passive"))
    )
    (net (code "69") (name "Net-(IC7-LX)") (class "Default")
      (node (ref "IC7") (pin "3") (pinfunction "LX_3") (pintype "bidirectional"))
      (node (ref "L13") (pin "2_1") (pinfunction "2_2_1") (pintype "passive"))
      (node (ref "L13") (pin "2_2") (pinfunction "2_2_2") (pintype "passive"))
      (node (ref "L13") (pin "2_3") (pinfunction "2_2_3") (pintype "passive"))
      (node (ref "L13") (pin "2_4") (pinfunction "2_2_4") (pintype "passive"))
      (node (ref "L13") (pin "2_5") (pinfunction "2_2_5") (pintype "passive"))
      (node (ref "L13") (pin "2_6") (pinfunction "2_2_6") (pintype "passive"))
      (node (ref "L13") (pin "2_7") (pinfunction "2_2_7") (pintype "passive"))
      (node (ref "L13") (pin "2_8") (pinfunction "2_2_8") (pintype "passive"))
      (node (ref "L13") (pin "2_9") (pinfunction "2_2_9") (pintype "passive"))
    )
    (net (code "70") (name "Net-(IC10-SW)") (class "Default")
      (node (ref "IC10") (pin "1") (pinfunction "SW_1") (pintype "output"))
      (node (ref "L14") (pin "2_1") (pinfunction "2_2_1") (pintype "passive"))
      (node (ref "L14") (pin "2_2") (pinfunction "2_2_2") (pintype "passive"))
      (node (ref "L14") (pin "2_3") (pinfunction "2_2_3") (pintype "passive"))
      (node (ref "L14") (pin "2_4") (pinfunction "2_2_4") (pintype "passive"))
      (node (ref "L14") (pin "2_5") (pinfunction "2_2_5") (pintype "passive"))
      (node (ref "L14") (pin "2_6") (pinfunction "2_2_6") (pintype "passive"))
      (node (ref "L14") (pin "2_7") (pinfunction "2_2_7") (pintype "passive"))
      (node (ref "L14") (pin "2_8") (pinfunction "2_2_8") (pintype "passive"))
      (node (ref "L14") (pin "2_9") (pinfunction "2_2_9") (pintype "passive"))
    )
    (net (code "71") (name "Net-(IC11-SW)") (class "Default")
      (node (ref "IC11") (pin "1") (pinfunction "SW_1") (pintype "output"))
      (node (ref "L16") (pin "2_1") (pinfunction "2_2_1") (pintype "passive"))
      (node (ref "L16") (pin "2_2") (pinfunction "2_2_2") (pintype "passive"))
      (node (ref "L16") (pin "2_3") (pinfunction "2_2_3") (pintype "passive"))
      (node (ref "L16") (pin "2_4") (pinfunction "2_2_4") (pintype "passive"))
      (node (ref "L16") (pin "2_5") (pinfunction "2_2_5") (pintype "passive"))
      (node (ref "L16") (pin "2_6") (pinfunction "2_2_6") (pintype "passive"))
      (node (ref "L16") (pin "2_7") (pinfunction "2_2_7") (pintype "passive"))
      (node (ref "L16") (pin "2_8") (pinfunction "2_2_8") (pintype "passive"))
      (node (ref "L16") (pin "2_9") (pinfunction "2_2_9") (pintype "passive"))
    )
    (net (code "72") (name "Net-(IC12-FB)") (class "Default")
      (node (ref "IC12") (pin "3") (pinfunction "FB_3") (pintype "bidirectional"))
      (node (ref "R12") (pin "P$1") (pinfunction "1_P$1") (pintype "passive"))
      (node (ref "R19") (pin "P$2") (pinfunction "2_P$2") (pintype "passive"))
    )
    (net (code "73") (name "Net-(IC12-L1-Pad8)") (class "Default")
      (node (ref "IC12") (pin "8") (pinfunction "L1_8") (pintype "bidirectional"))
      (node (ref "IC12") (pin "9") (pinfunction "L1_9") (pintype "bidirectional"))
      (node (ref "L21") (pin "2_1") (pinfunction "2_2_1") (pintype "passive"))
      (node (ref "L21") (pin "2_2") (pinfunction "2_2_2") (pintype "passive"))
      (node (ref "L21") (pin "2_3") (pinfunction "2_2_3") (pintype "passive"))
      (node (ref "L21") (pin "2_4") (pinfunction "2_2_4") (pintype "passive"))
      (node (ref "L21") (pin "2_5") (pinfunction "2_2_5") (pintype "passive"))
      (node (ref "L21") (pin "2_6") (pinfunction "2_2_6") (pintype "passive"))
      (node (ref "L21") (pin "2_7") (pinfunction "2_2_7") (pintype "passive"))
      (node (ref "L21") (pin "2_8") (pinfunction "2_2_8") (pintype "passive"))
      (node (ref "L21") (pin "2_9") (pinfunction "2_2_9") (pintype "passive"))
    )
    (net (code "74") (name "Net-(IC12-L2-Pad6)") (class "Default")
      (node (ref "IC12") (pin "6") (pinfunction "L2_6") (pintype "bidirectional"))
      (node (ref "IC12") (pin "7") (pinfunction "L2_7") (pintype "bidirectional"))
      (node (ref "L21") (pin "1_1") (pinfunction "1_1_1") (pintype "passive"))
      (node (ref "L21") (pin "1_2") (pinfunction "1_1_2") (pintype "passive"))
      (node (ref "L21") (pin "1_3") (pinfunction "1_1_3") (pintype "passive"))
      (node (ref "L21") (pin "1_4") (pinfunction "1_1_4") (pintype "passive"))
      (node (ref "L21") (pin "1_5") (pinfunction "1_1_5") (pintype "passive"))
      (node (ref "L21") (pin "1_6") (pinfunction "1_1_6") (pintype "passive"))
      (node (ref "L21") (pin "1_7") (pinfunction "1_1_7") (pintype "passive"))
      (node (ref "L21") (pin "1_8") (pinfunction "1_1_8") (pintype "passive"))
      (node (ref "L21") (pin "1_9") (pinfunction "1_1_9") (pintype "passive"))
    )
    (net (code "75") (name "Net-(L7-2)") (class "Default")
      (node (ref "L7") (pin "P$2") (pinfunction "2_P$2") (pintype "passive"))
      (node (ref "U$2") (pin "1") (pinfunction "B2_1") (pintype "bidirectional"))
    )
    (net (code "76") (name "Net-(L12-2)") (class "Default")
      (node (ref "L12") (pin "P$2") (pinfunction "2_P$2") (pintype "passive"))
      (node (ref "R40") (pin "P$1") (pinfunction "1_P$1") (pintype "passive"))
    )
    (net (code "77") (name "Net-(L20-2)") (class "Default")
      (node (ref "L20") (pin "P$2") (pinfunction "2_P$2") (pintype "passive"))
      (node (ref "R39") (pin "P$1") (pinfunction "1_P$1") (pintype "passive"))
    )
    (net (code "78") (name "Net-(R2-1)") (class "Default")
      (node (ref "LED1") (pin "A") (pinfunction "A_A") (pintype "passive"))
      (node (ref "R2") (pin "P$1") (pinfunction "1_P$1") (pintype "passive"))
    )
    (net (code "79") (name "Net-(R3-1)") (class "Default")
      (node (ref "LED2") (pin "A") (pinfunction "A_A") (pintype "passive"))
      (node (ref "R3") (pin "P$1") (pinfunction "1_P$1") (pintype "passive"))
    )
    (net (code "80") (name "Net-(R5-1)") (class "Default")
      (node (ref "LED3") (pin "A") (pinfunction "A_A") (pintype "passive"))
      (node (ref "R5") (pin "P$1") (pinfunction "1_P$1") (pintype "passive"))
    )
    (net (code "81") (name "Net-(R6-1)") (class "Default")
      (node (ref "LED4") (pin "A") (pinfunction "A_A") (pintype "passive"))
      (node (ref "R6") (pin "P$1") (pinfunction "1_P$1") (pintype "passive"))
    )
    (net (code "82") (name "Net-(R11-2)") (class "Default")
      (node (ref "LED5") (pin "C") (pinfunction "C_C") (pintype "passive"))
      (node (ref "R11") (pin "P$2") (pinfunction "2_P$2") (pintype "passive"))
    )
    (net (code "83") (name "Net-(R31-1)") (class "Default")
      (node (ref "LED6") (pin "C") (pinfunction "C_C") (pintype "passive"))
      (node (ref "R31") (pin "P$1") (pinfunction "1_P$1") (pintype "passive"))
    )
    (net (code "84") (name "Net-(R32-1)") (class "Default")
      (node (ref "LED7") (pin "C") (pinfunction "C_C") (pintype "passive"))
      (node (ref "R32") (pin "P$1") (pinfunction "1_P$1") (pintype "passive"))
    )
    (net (code "85") (name "Net-(R33-1)") (class "Default")
      (node (ref "LED8") (pin "C") (pinfunction "C_C") (pintype "passive"))
      (node (ref "R33") (pin "P$1") (pinfunction "1_P$1") (pintype "passive"))
    )
    (net (code "86") (name "Net-(R34-1)") (class "Default")
      (node (ref "LED9") (pin "C") (pinfunction "C_C") (pintype "passive"))
      (node (ref "R34") (pin "P$1") (pinfunction "1_P$1") (pintype "passive"))
    )
    (net (code "87") (name "PA_EN") (class "Default")
      (node (ref "IC1") (pin "20") (pinfunction "GPIO_3_20") (pintype "bidirectional"))
      (node (ref "IC12") (pin "12") (pinfunction "EN_12") (pintype "bidirectional"))
      (node (ref "R3") (pin "P$2") (pinfunction "2_P$2") (pintype "passive"))
    )
    (net (code "88") (name "RADIO1_CS") (class "Default")
      (node (ref "IC1") (pin "15") (pinfunction "NSEL_15") (pintype "bidirectional"))
      (node (ref "IC5") (pin "P14") (pinfunction "PD9_P14") (pintype "bidirectional"))
    )
    (net (code "89") (name "RADIO1_GPIO0") (class "Default")
      (node (ref "IC1") (pin "9") (pinfunction "GPIO_0_9") (pintype "bidirectional"))
      (node (ref "IC5") (pin "M15") (pinfunction "PD13_M15") (pintype "bidirectional"))
    )
    (net (code "90") (name "RADIO1_GPIO1") (class "Default")
      (node (ref "IC1") (pin "10") (pinfunction "GPIO_1_10") (pintype "bidirectional"))
      (node (ref "IC5") (pin "P15") (pinfunction "PD8_P15") (pintype "bidirectional"))
    )
    (net (code "91") (name "RADIO1_SDN") (class "Default")
      (node (ref "IC1") (pin "1") (pinfunction "SDN_1") (pintype "bidirectional"))
      (node (ref "IC5") (pin "R11") (pinfunction "PE15_R11") (pintype "bidirectional"))
      (node (ref "R1") (pin "P$2") (pinfunction "2_P$2") (pintype "passive"))
    )
    (net (code "92") (name "RADIO1_VREG1") (class "Default")
      (node (ref "C66") (pin "P$2") (pinfunction "2_P$2") (pintype "passive"))
      (node (ref "IC13") (pin "19") (pinfunction "VREG1_19") (pintype "bidirectional"))
      (node (ref "R28") (pin "P$1") (pinfunction "1_P$1") (pintype "passive"))
    )
    (net (code "93") (name "RADIO1_VREG2") (class "Default")
      (node (ref "C5") (pin "P$2") (pinfunction "2_P$2") (pintype "passive"))
      (node (ref "IC13") (pin "5") (pinfunction "VREG2_5") (pintype "bidirectional"))
      (node (ref "R24") (pin "P$2") (pinfunction "2_P$2") (pintype "passive"))
    )
    (net (code "94") (name "RADIO1_VREG_SW") (class "Default")
      (node (ref "C23") (pin "P$2") (pinfunction "2_P$2") (pintype "passive"))
      (node (ref "C67") (pin "P$2") (pinfunction "2_P$2") (pintype "passive"))
      (node (ref "IC5") (pin "N15") (pinfunction "PD10_N15") (pintype "bidirectional"))
      (node (ref "R24") (pin "P$1") (pinfunction "1_P$1") (pintype "passive"))
      (node (ref "R28") (pin "P$2") (pinfunction "2_P$2") (pintype "passive"))
      (node (ref "R30") (pin "P$2") (pinfunction "2_P$2") (pintype "passive"))
      (node (ref "R38") (pin "P$1") (pinfunction "1_P$1") (pintype "passive"))
    )
    (net (code "95") (name "RADIO2_CS") (class "Default")
      (node (ref "IC2") (pin "15") (pinfunction "NSEL_15") (pintype "bidirectional"))
      (node (ref "IC5") (pin "L15") (pinfunction "PG2_L15") (pintype "bidirectional"))
    )
    (net (code "96") (name "RADIO2_GPIO0") (class "Default")
      (node (ref "IC2") (pin "9") (pinfunction "GPIO_0_9") (pintype "bidirectional"))
      (node (ref "IC5") (pin "K15") (pinfunction "PG3_K15") (pintype "bidirectional"))
    )
    (net (code "97") (name "RADIO2_GPIO1") (class "Default")
      (node (ref "IC2") (pin "10") (pinfunction "GPIO_1_10") (pintype "bidirectional"))
      (node (ref "IC5") (pin "C11") (pinfunction "PD5_C11") (pintype "bidirectional"))
    )
    (net (code "98") (name "RADIO2_SDN") (class "Default")
      (node (ref "IC2") (pin "1") (pinfunction "SDN_1") (pintype "bidirectional"))
      (node (ref "IC5") (pin "J15") (pinfunction "PG6_J15") (pintype "bidirectional"))
      (node (ref "R4") (pin "P$2") (pinfunction "2_P$2") (pintype "passive"))
    )
    (net (code "99") (name "RX_ACTIVE") (class "Default")
      (node (ref "IC2") (pin "19") (pinfunction "GPIO_2_19") (pintype "bidirectional"))
      (node (ref "R5") (pin "P$2") (pinfunction "2_P$2") (pintype "passive"))
      (node (ref "U$2") (pin "4") (pinfunction "V2_4") (pintype "bidirectional"))
    )
    (net (code "100") (name "SD_CS") (class "Default")
      (node (ref "IC5") (pin "R2") (pinfunction "PA3_R2") (pintype "bidirectional"))
      (node (ref "U$1") (pin "2") (pinfunction "/CS_2") (pintype "bidirectional"))
    )
    (net (code "101") (name "SOLAR_OUT") (class "Default")
      (node (ref "C47") (pin "2") (pinfunction "2_2") (pintype "passive"))
      (node (ref "IC16") (pin "1") (pinfunction "SENSE1+_1") (pintype "input"))
      (node (ref "IC7") (pin "4") (pinfunction "VOUT_4") (pintype "bidirectional"))
      (node (ref "IC7") (pin "6") (pinfunction "ICTRL-_6") (pintype "bidirectional"))
      (node (ref "IC7") (pin "7") (pinfunction "ICTRL+_7") (pintype "bidirectional"))
      (node (ref "R13") (pin "P$2") (pinfunction "2_P$2") (pintype "passive"))
      (node (ref "R20") (pin "P$1") (pinfunction "1_P$1") (pintype "passive"))
    )
    (net (code "102") (name "SPI_MISO") (class "Default")
      (node (ref "IC1") (pin "13") (pinfunction "SDO_13") (pintype "bidirectional"))
      (node (ref "IC2") (pin "13") (pinfunction "SDO_13") (pintype "bidirectional"))
      (node (ref "IC5") (pin "R14") (pinfunction "PB14_R14") (pintype "bidirectional"))
      (node (ref "U$1") (pin "7") (pinfunction "DO_7") (pintype "bidirectional"))
    )
    (net (code "103") (name "SPI_MOSI") (class "Default")
      (node (ref "IC1") (pin "14") (pinfunction "SDI_14") (pintype "bidirectional"))
      (node (ref "IC2") (pin "14") (pinfunction "SDI_14") (pintype "bidirectional"))
      (node (ref "IC5") (pin "R15") (pinfunction "PB15_R15") (pintype "bidirectional"))
      (node (ref "U$1") (pin "3") (pinfunction "DI_3") (pintype "bidirectional"))
    )
    (net (code "104") (name "SPI_SCK") (class "Default")
      (node (ref "IC1") (pin "12") (pinfunction "SCLK_12") (pintype "bidirectional"))
      (node (ref "IC2") (pin "12") (pinfunction "SCLK_12") (pintype "bidirectional"))
      (node (ref "IC5") (pin "P13") (pinfunction "PB13_P13") (pintype "bidirectional"))
      (node (ref "U$1") (pin "5") (pinfunction "CLK_5") (pintype "bidirectional"))
    )
    (net (code "105") (name "SWCLK") (class "Default")
      (node (ref "IC5") (pin "A14") (pinfunction "PA14_A14") (pintype "bidirectional"))
      (node (ref "JP3") (pin "2") (pinfunction "2_2") (pintype "passive"))
    )
    (net (code "106") (name "SWDIO") (class "Default")
      (node (ref "IC5") (pin "A15") (pinfunction "PA13_A15") (pintype "bidirectional"))
      (node (ref "JP3") (pin "4") (pinfunction "4_4") (pintype "passive"))
    )
    (net (code "107") (name "SWO") (class "Default")
      (node (ref "IC5") (pin "A10") (pinfunction "PB3_A10") (pintype "bidirectional"))
      (node (ref "JP3") (pin "6") (pinfunction "6_6") (pintype "passive"))
    )
    (net (code "108") (name "TIMEPULSE") (class "Default")
      (node (ref "IC4") (pin "4_TIMEPULSE") (pinfunction "4_TIMEPULSE_4_TIMEPULSE") (pintype "bidirectional"))
      (node (ref "IC5") (pin "R4") (pinfunction "PB1_R4") (pintype "bidirectional"))
      (node (ref "R11") (pin "P$1") (pinfunction "1_P$1") (pintype "passive"))
    )
    (net (code "109") (name "TX_ACTIVE") (class "Default")
      (node (ref "IC2") (pin "20") (pinfunction "GPIO_3_20") (pintype "bidirectional"))
      (node (ref "R6") (pin "P$2") (pinfunction "2_P$2") (pintype "passive"))
      (node (ref "U$2") (pin "6") (pinfunction "V1_6") (pintype "bidirectional"))
    )
    (net (code "110") (name "UART_RXD") (class "Default")
      (node (ref "IC5") (pin "N2") (pinfunction "PA1_N2") (pintype "bidirectional"))
      (node (ref "JP3") (pin "10") (pinfunction "10_10") (pintype "passive"))
    )
    (net (code "111") (name "UART_TXD") (class "Default")
      (node (ref "IC5") (pin "N3") (pinfunction "PA0_N3") (pintype "bidirectional"))
      (node (ref "JP3") (pin "11") (pinfunction "11_11") (pintype "passive"))
    )
    (net (code "112") (name "VBAT") (class "Default")
      (node (ref "IC16") (pin "2") (pinfunction "SENSE1-_2") (pintype "input"))
      (node (ref "IC16") (pin "3") (pinfunction "SENSE2+_3") (pintype "input"))
      (node (ref "JP4") (pin "6") (pinfunction "6_6") (pintype "passive"))
      (node (ref "R15") (pin "P$2") (pinfunction "2_P$2") (pintype "passive"))
      (node (ref "R20") (pin "P$2") (pinfunction "2_P$2") (pintype "passive"))
      (node (ref "R21") (pin "P$1") (pinfunction "1_P$1") (pintype "passive"))
      (node (ref "SJ3") (pin "2") (pinfunction "2_2") (pintype "passive"))
    )
    (net (code "113") (name "VBAT_DIFF") (class "Default")
      (node (ref "IC5") (pin "P5") (pinfunction "PC5_P5") (pintype "bidirectional"))
      (node (ref "R15") (pin "P$1") (pinfunction "1_P$1") (pintype "passive"))
      (node (ref "R16") (pin "P$2") (pinfunction "2_P$2") (pintype "passive"))
    )
    (net (code "114") (name "VBAT_OUT") (class "Default")
      (node (ref "C37") (pin "2") (pinfunction "2_2") (pintype "passive"))
      (node (ref "C39") (pin "2") (pinfunction "2_2") (pintype "passive"))
      (node (ref "C53") (pin "P$1") (pinfunction "1_P$1") (pintype "passive"))
      (node (ref "C7") (pin "2") (pinfunction "2_2") (pintype "passive"))
      (node (ref "C80") (pin "P$1") (pinfunction "1_P$1") (pintype "passive"))
      (node (ref "C82") (pin "P$1") (pinfunction "1_P$1") (pintype "passive"))
      (node (ref "IC10") (pin "5") (pinfunction "VIN_5") (pintype "input"))
      (node (ref "IC11") (pin "4") (pinfunction "EN_4") (pintype "input"))
      (node (ref "IC11") (pin "5") (pinfunction "VIN_5") (pintype "input"))
      (node (ref "IC12") (pin "10") (pinfunction "VIN_10") (pintype "bidirectional"))
      (node (ref "IC12") (pin "11") (pinfunction "VIN_11") (pintype "bidirectional"))
      (node (ref "IC14") (pin "1") (pinfunction "VIN_1") (pintype "input"))
      (node (ref "IC16") (pin "4") (pinfunction "SENSE2-_4") (pintype "input"))
      (node (ref "IC8") (pin "1") (pinfunction "VIN_1") (pintype "input"))
      (node (ref "IC9") (pin "1") (pinfunction "VIN_1") (pintype "input"))
      (node (ref "IC9") (pin "3") (pinfunction "SHDN*_3") (pintype "input"))
      (node (ref "R21") (pin "P$2") (pinfunction "2_P$2") (pintype "passive"))
    )
    (net (code "115") (name "VCC") (class "Default")
      (node (ref "C10") (pin "P$2") (pinfunction "2_P$2") (pintype "passive"))
      (node (ref "C11") (pin "P$2") (pinfunction "2_P$2") (pintype "passive"))
      (node (ref "C15") (pin "P$1") (pinfunction "1_P$1") (pintype "passive"))
      (node (ref "C18") (pin "P$2") (pinfunction "2_P$2") (pintype "passive"))
      (node (ref "C19") (pin "P$2") (pinfunction "2_P$2") (pintype "passive"))
      (node (ref "C20") (pin "P$2") (pinfunction "2_P$2") (pintype "passive"))
      (node (ref "C25") (pin "P$2") (pinfunction "2_P$2") (pintype "passive"))
      (node (ref "C29") (pin "P$1") (pinfunction "1_P$1") (pintype "passive"))
      (node (ref "C30") (pin "P$1") (pinfunction "1_P$1") (pintype "passive"))
      (node (ref "C31") (pin "P$1") (pinfunction "1_P$1") (pintype "passive"))
      (node (ref "C32") (pin "P$1") (pinfunction "1_P$1") (pintype "passive"))
      (node (ref "C33") (pin "P$1") (pinfunction "1_P$1") (pintype "passive"))
      (node (ref "C34") (pin "P$1") (pinfunction "1_P$1") (pintype "passive"))
      (node (ref "C35") (pin "P$1") (pinfunction "1_P$1") (pintype "passive"))
      (node (ref "C36") (pin "P$1") (pinfunction "1_P$1") (pintype "passive"))
      (node (ref "C38") (pin "P$1") (pinfunction "1_P$1") (pintype "passive"))
      (node (ref "C48") (pin "P$1") (pinfunction "1_P$1") (pintype "passive"))
      (node (ref "C50") (pin "2") (pinfunction "2_2") (pintype "passive"))
      (node (ref "C9") (pin "P$2") (pinfunction "2_P$2") (pintype "passive"))
      (node (ref "IC1") (pin "6") (pinfunction "VBATA_6") (pintype "bidirectional"))
      (node (ref "IC1") (pin "8") (pinfunction "VBATD_8") (pintype "bidirectional"))
      (node (ref "IC11") (pin "3") (pinfunction "FB_3") (pintype "input"))
      (node (ref "IC2") (pin "6") (pinfunction "VBATA_6") (pintype "bidirectional"))
      (node (ref "IC2") (pin "8") (pinfunction "VBATD_8") (pintype "bidirectional"))
      (node (ref "IC3") (pin "2") (pinfunction "CSB_2") (pintype "bidirectional"))
      (node (ref "IC3") (pin "5") (pinfunction "SDO_5") (pintype "bidirectional"))
      (node (ref "IC3") (pin "6") (pinfunction "VDD_IO_6") (pintype "bidirectional"))
      (node (ref "IC3") (pin "8") (pinfunction "VDD_8") (pintype "bidirectional"))
      (node (ref "IC4") (pin "6_V_BCKP") (pinfunction "6_V_BCKP_6_V_BCKP") (pintype "bidirectional"))
      (node (ref "IC4") (pin "7_VCC_IO") (pinfunction "7_VCC_IO_7_VCC_IO") (pintype "power_in"))
      (node (ref "IC5") (pin "C1") (pinfunction "VBAT_C1") (pintype "bidirectional"))
      (node (ref "IC5") (pin "C5") (pinfunction "VDD1_C5") (pintype "bidirectional"))
      (node (ref "IC5") (pin "C6") (pinfunction "PDR_ON_C6") (pintype "bidirectional"))
      (node (ref "IC5") (pin "C7") (pinfunction "VDD2_C7") (pintype "bidirectional"))
      (node (ref "IC5") (pin "C8") (pinfunction "VDD3_C8") (pintype "bidirectional"))
      (node (ref "IC5") (pin "C9") (pinfunction "VDD4_C9") (pintype "bidirectional"))
      (node (ref "IC5") (pin "F3") (pinfunction "VDD5_F3") (pintype "bidirectional"))
      (node (ref "IC5") (pin "G13") (pinfunction "VDD7_G13") (pintype "bidirectional"))
      (node (ref "IC5") (pin "G3") (pinfunction "VDD6_G3") (pintype "bidirectional"))
      (node (ref "IC5") (pin "H13") (pinfunction "VDD8_H13") (pintype "bidirectional"))
      (node (ref "IC5") (pin "J12") (pinfunction "VDD9_J12") (pintype "bidirectional"))
      (node (ref "IC5") (pin "J13") (pinfunction "VDD10_J13") (pintype "bidirectional"))
      (node (ref "IC5") (pin "K4") (pinfunction "VDD11_K4") (pintype "bidirectional"))
      (node (ref "IC5") (pin "N10") (pinfunction "VDD14_N10") (pintype "bidirectional"))
      (node (ref "IC5") (pin "N8") (pinfunction "VDD12_N8") (pintype "bidirectional"))
      (node (ref "IC5") (pin "N9") (pinfunction "VDD13_N9") (pintype "bidirectional"))
      (node (ref "IC5") (pin "P1") (pinfunction "VREF+_P1") (pintype "bidirectional"))
      (node (ref "IC5") (pin "R1") (pinfunction "VDDA_R1") (pintype "bidirectional"))
      (node (ref "JP3") (pin "1") (pinfunction "1_1") (pintype "passive"))
      (node (ref "JP4") (pin "1") (pinfunction "1_1") (pintype "passive"))
      (node (ref "L16") (pin "1_1") (pinfunction "1_1_1") (pintype "passive"))
      (node (ref "L16") (pin "1_2") (pinfunction "1_1_2") (pintype "passive"))
      (node (ref "L16") (pin "1_3") (pinfunction "1_1_3") (pintype "passive"))
      (node (ref "L16") (pin "1_4") (pinfunction "1_1_4") (pintype "passive"))
      (node (ref "L16") (pin "1_5") (pinfunction "1_1_5") (pintype "passive"))
      (node (ref "L16") (pin "1_6") (pinfunction "1_1_6") (pintype "passive"))
      (node (ref "L16") (pin "1_7") (pinfunction "1_1_7") (pintype "passive"))
      (node (ref "L16") (pin "1_8") (pinfunction "1_1_8") (pintype "passive"))
      (node (ref "L16") (pin "1_9") (pinfunction "1_1_9") (pintype "passive"))
      (node (ref "L5") (pin "P$2") (pinfunction "2_P$2") (pintype "passive"))
      (node (ref "L8") (pin "P$2") (pinfunction "2_P$2") (pintype "passive"))
      (node (ref "LED5") (pin "A") (pinfunction "A_A") (pintype "passive"))
      (node (ref "LED6") (pin "A") (pinfunction "A_A") (pintype "passive"))
      (node (ref "LED7") (pin "A") (pinfunction "A_A") (pintype "passive"))
      (node (ref "LED8") (pin "A") (pinfunction "A_A") (pintype "passive"))
      (node (ref "LED9") (pin "A") (pinfunction "A_A") (pintype "passive"))
      (node (ref "R1") (pin "P$1") (pinfunction "1_P$1") (pintype "passive"))
      (node (ref "R4") (pin "P$1") (pinfunction "1_P$1") (pintype "passive"))
      (node (ref "R7") (pin "P$2") (pinfunction "2_P$2") (pintype "passive"))
      (node (ref "R8") (pin "P$2") (pinfunction "2_P$2") (pintype "passive"))
      (node (ref "R9") (pin "P$1") (pinfunction "1_P$1") (pintype "passive"))
      (node (ref "SJ2") (pin "3") (pinfunction "3_3") (pintype "passive"))
      (node (ref "U$1") (pin "4") (pinfunction "VDD_4") (pintype "bidirectional"))
      (node (ref "U$3") (pin "4") (pinfunction "VCC_4") (pintype "bidirectional"))
    )
    (net (code "116") (name "VCC2V7") (class "Default")
      (node (ref "C81") (pin "P$1") (pinfunction "1_P$1") (pintype "passive"))
      (node (ref "IC16") (pin "10") (pinfunction "VDD_10") (pintype "power_in"))
      (node (ref "IC9") (pin "5") (pinfunction "VOUT_5") (pintype "output"))
    )
    (net (code "117") (name "VCC3V3") (class "Default")
      (node (ref "C49") (pin "2") (pinfunction "2_2") (pintype "passive"))
      (node (ref "C56") (pin "P$2") (pinfunction "2_P$2") (pintype "passive"))
      (node (ref "L14") (pin "1_1") (pinfunction "1_1_1") (pintype "passive"))
      (node (ref "L14") (pin "1_2") (pinfunction "1_1_2") (pintype "passive"))
      (node (ref "L14") (pin "1_3") (pinfunction "1_1_3") (pintype "passive"))
      (node (ref "L14") (pin "1_4") (pinfunction "1_1_4") (pintype "passive"))
      (node (ref "L14") (pin "1_5") (pinfunction "1_1_5") (pintype "passive"))
      (node (ref "L14") (pin "1_6") (pinfunction "1_1_6") (pintype "passive"))
      (node (ref "L14") (pin "1_7") (pinfunction "1_1_7") (pintype "passive"))
      (node (ref "L14") (pin "1_8") (pinfunction "1_1_8") (pintype "passive"))
      (node (ref "L14") (pin "1_9") (pinfunction "1_1_9") (pintype "passive"))
      (node (ref "R17") (pin "P$2") (pinfunction "2_P$2") (pintype "passive"))
      (node (ref "SJ1") (pin "1") (pinfunction "1_1") (pintype "passive"))
      (node (ref "SJ2") (pin "1") (pinfunction "1_1") (pintype "passive"))
    )
    (net (code "118") (name "VCC_PA") (class "Default")
      (node (ref "C61") (pin "P$2") (pinfunction "2_P$2") (pintype "passive"))
      (node (ref "C62") (pin "2") (pinfunction "2_2") (pintype "passive"))
      (node (ref "C65") (pin "P$2") (pinfunction "2_P$2") (pintype "passive"))
      (node (ref "C68") (pin "P$2") (pinfunction "2_P$2") (pintype "passive"))
      (node (ref "C69") (pin "P$2") (pinfunction "2_P$2") (pintype "passive"))
      (node (ref "C72") (pin "2") (pinfunction "2_2") (pintype "passive"))
      (node (ref "C73") (pin "2") (pinfunction "2_2") (pintype "passive"))
      (node (ref "C79") (pin "P$2") (pinfunction "2_P$2") (pintype "passive"))
      (node (ref "IC12") (pin "4") (pinfunction "VOUT_4") (pintype "bidirectional"))
      (node (ref "IC12") (pin "5") (pinfunction "VOUT_5") (pintype "bidirectional"))
      (node (ref "IC13") (pin "1") (pinfunction "VCC1_1") (pintype "bidirectional"))
      (node (ref "IC13") (pin "2") (pinfunction "VCC2_2") (pintype "bidirectional"))
      (node (ref "IC13") (pin "22") (pinfunction "VBIAS_22") (pintype "bidirectional"))
      (node (ref "IC13") (pin "3") (pinfunction "VCC3_3") (pintype "bidirectional"))
      (node (ref "L11") (pin "P$2") (pinfunction "2_P$2") (pintype "passive"))
      (node (ref "R12") (pin "P$2") (pinfunction "2_P$2") (pintype "passive"))
      (node (ref "R38") (pin "P$2") (pinfunction "2_P$2") (pintype "passive"))
    )
    (net (code "119") (name "VSOLAR") (class "Default")
      (node (ref "C46") (pin "2") (pinfunction "2_2") (pintype "passive"))
      (node (ref "IC7") (pin "1") (pinfunction "VINSNS_1") (pintype "bidirectional"))
      (node (ref "IC7") (pin "8") (pinfunction "XSHUNT_8") (pintype "bidirectional"))
      (node (ref "JP2") (pin "P$1") (pinfunction "1_P$1") (pintype "passive"))
      (node (ref "JP4") (pin "2") (pinfunction "2_2") (pintype "passive"))
      (node (ref "L13") (pin "1_1") (pinfunction "1_1_1") (pintype "passive"))
      (node (ref "L13") (pin "1_2") (pinfunction "1_1_2") (pintype "passive"))
      (node (ref "L13") (pin "1_3") (pinfunction "1_1_3") (pintype "passive"))
      (node (ref "L13") (pin "1_4") (pinfunction "1_1_4") (pintype "passive"))
      (node (ref "L13") (pin "1_5") (pinfunction "1_1_5") (pintype "passive"))
      (node (ref "L13") (pin "1_6") (pinfunction "1_1_6") (pintype "passive"))
      (node (ref "L13") (pin "1_7") (pinfunction "1_1_7") (pintype "passive"))
      (node (ref "L13") (pin "1_8") (pinfunction "1_1_8") (pintype "passive"))
      (node (ref "L13") (pin "1_9") (pinfunction "1_1_9") (pintype "passive"))
      (node (ref "R23") (pin "P$2") (pinfunction "2_P$2") (pintype "passive"))
    )
    (net (code "120") (name "VSOLAR_DIFF") (class "Default")
      (node (ref "IC5") (pin "N5") (pinfunction "PC4_N5") (pintype "bidirectional"))
      (node (ref "R23") (pin "P$1") (pinfunction "1_P$1") (pintype "passive"))
      (node (ref "R25") (pin "P$2") (pinfunction "2_P$2") (pintype "passive"))
    )
    (net (code "121") (name "unconnected-(IC1-NIRQ-Pad11)") (class "Default")
      (node (ref "IC1") (pin "11") (pinfunction "NIRQ_11") (pintype "bidirectional"))
    )
    (net (code "122") (name "unconnected-(IC1-RXN-Pad3)") (class "Default")
      (node (ref "IC1") (pin "3") (pinfunction "RXN_3") (pintype "bidirectional"))
    )
    (net (code "123") (name "unconnected-(IC1-RXP-Pad2)") (class "Default")
      (node (ref "IC1") (pin "2") (pinfunction "RXP_2") (pintype "bidirectional"))
    )
    (net (code "124") (name "unconnected-(IC1-TXRAMP-Pad7)") (class "Default")
      (node (ref "IC1") (pin "7") (pinfunction "TXRAMP_7") (pintype "bidirectional"))
    )
    (net (code "125") (name "unconnected-(IC2-NIRQ-Pad11)") (class "Default")
      (node (ref "IC2") (pin "11") (pinfunction "NIRQ_11") (pintype "bidirectional"))
    )
    (net (code "126") (name "unconnected-(IC2-TXRAMP-Pad7)") (class "Default")
      (node (ref "IC2") (pin "7") (pinfunction "TXRAMP_7") (pintype "bidirectional"))
    )
    (net (code "127") (name "unconnected-(IC4-Pad2_TXD1)") (class "Default")
      (node (ref "IC4") (pin "2_TXD1") (pinfunction "2_TXD1_2_TXD1") (pintype "bidirectional"))
    )
    (net (code "128") (name "unconnected-(IC4-Pad3_RXD1)") (class "Default")
      (node (ref "IC4") (pin "3_RXD1") (pinfunction "3_RXD1_3_RXD1") (pintype "bidirectional"))
    )
    (net (code "129") (name "unconnected-(IC4-Pad5_EXTINT0)") (class "Default")
      (node (ref "IC4") (pin "5_EXTINT0") (pinfunction "5_EXTINT0_5_EXTINT0") (pintype "bidirectional"))
    )
    (net (code "130") (name "unconnected-(IC4-Pad13_ANTON)") (class "Default")
      (node (ref "IC4") (pin "13_ANTON") (pinfunction "13_ANTON_13_ANTON") (pintype "bidirectional"))
    )
    (net (code "131") (name "unconnected-(IC4-Pad15_RESERVED)") (class "Default")
      (node (ref "IC4") (pin "15_RESERVED") (pinfunction "15_RESERVED_15_RESERVED") (pintype "bidirectional"))
    )
    (net (code "132") (name "unconnected-(IC4-Pad18_RESERVED)") (class "Default")
      (node (ref "IC4") (pin "18_RESERVED") (pinfunction "18_RESERVED_18_RESERVED") (pintype "bidirectional"))
    )
    (net (code "133") (name "unconnected-(IC5A-PA5-PadP4)") (class "Default")
      (node (ref "IC5") (pin "P4") (pinfunction "PA5_P4") (pintype "bidirectional"))
    )
    (net (code "134") (name "unconnected-(IC5A-PA7-PadR3)") (class "Default")
      (node (ref "IC5") (pin "R3") (pinfunction "PA7_R3") (pintype "bidirectional"))
    )
    (net (code "135") (name "unconnected-(IC5A-PA9-PadE15)") (class "Default")
      (node (ref "IC5") (pin "E15") (pinfunction "PA9_E15") (pintype "bidirectional"))
    )
    (net (code "136") (name "unconnected-(IC5A-PA10-PadD15)") (class "Default")
      (node (ref "IC5") (pin "D15") (pinfunction "PA10_D15") (pintype "bidirectional"))
    )
    (net (code "137") (name "unconnected-(IC5A-PA11-PadC15)") (class "Default")
      (node (ref "IC5") (pin "C15") (pinfunction "PA11_C15") (pintype "bidirectional"))
    )
    (net (code "138") (name "unconnected-(IC5A-PA12-PadB15)") (class "Default")
      (node (ref "IC5") (pin "B15") (pinfunction "PA12_B15") (pintype "bidirectional"))
    )
    (net (code "139") (name "unconnected-(IC5A-PA15-PadA13)") (class "Default")
      (node (ref "IC5") (pin "A13") (pinfunction "PA15_A13") (pintype "bidirectional"))
    )
    (net (code "140") (name "unconnected-(IC5A-PB2-PadM6)") (class "Default")
      (node (ref "IC5") (pin "M6") (pinfunction "PB2_M6") (pintype "bidirectional"))
    )
    (net (code "141") (name "unconnected-(IC5A-PB4-PadA9)") (class "Default")
      (node (ref "IC5") (pin "A9") (pinfunction "PB4_A9") (pintype "bidirectional"))
    )
    (net (code "142") (name "unconnected-(IC5A-PB5-PadA6)") (class "Default")
      (node (ref "IC5") (pin "A6") (pinfunction "PB5_A6") (pintype "bidirectional"))
    )
    (net (code "143") (name "unconnected-(IC5A-PB8-PadA5)") (class "Default")
      (node (ref "IC5") (pin "A5") (pinfunction "PB8_A5") (pintype "bidirectional"))
    )
    (net (code "144") (name "unconnected-(IC5A-PB9-PadB4)") (class "Default")
      (node (ref "IC5") (pin "B4") (pinfunction "PB9_B4") (pintype "bidirectional"))
    )
    (net (code "145") (name "unconnected-(IC5A-PB12-PadP12)") (class "Default")
      (node (ref "IC5") (pin "P12") (pinfunction "PB12_P12") (pintype "bidirectional"))
    )
    (net (code "146") (name "unconnected-(IC5A-PC0-PadM2)") (class "Default")
      (node (ref "IC5") (pin "M2") (pinfunction "PC0_M2") (pintype "bidirectional"))
    )
    (net (code "147") (name "unconnected-(IC5A-PC1-PadM3)") (class "Default")
      (node (ref "IC5") (pin "M3") (pinfunction "PC1_M3") (pintype "bidirectional"))
    )
    (net (code "148") (name "unconnected-(IC5A-PC2-PadM4)") (class "Default")
      (node (ref "IC5") (pin "M4") (pinfunction "PC2_M4") (pintype "bidirectional"))
    )
    (net (code "149") (name "unconnected-(IC5A-PC3-PadM5)") (class "Default")
      (node (ref "IC5") (pin "M5") (pinfunction "PC3_M5") (pintype "bidirectional"))
    )
    (net (code "150") (name "unconnected-(IC5A-PC10-PadB14)") (class "Default")
      (node (ref "IC5") (pin "B14") (pinfunction "PC10_B14") (pintype "bidirectional"))
    )
    (net (code "151") (name "unconnected-(IC5A-PC11-PadB13)") (class "Default")
      (node (ref "IC5") (pin "B13") (pinfunction "PC11_B13") (pintype "bidirectional"))
    )
    (net (code "152") (name "unconnected-(IC5A-PC12-PadA12)") (class "Default")
      (node (ref "IC5") (pin "A12") (pinfunction "PC12_A12") (pintype "bidirectional"))
    )
    (net (code "153") (name "unconnected-(IC5A-PC14-PadE1)") (class "Default")
      (node (ref "IC5") (pin "E1") (pinfunction "PC14_E1") (pintype "bidirectional"))
    )
    (net (code "154") (name "unconnected-(IC5A-PC15-PadF1)") (class "Default")
      (node (ref "IC5") (pin "F1") (pinfunction "PC15_F1") (pintype "bidirectional"))
    )
    (net (code "155") (name "unconnected-(IC5A-PD0-PadB12)") (class "Default")
      (node (ref "IC5") (pin "B12") (pinfunction "PD0_B12") (pintype "bidirectional"))
    )
    (net (code "156") (name "unconnected-(IC5A-PD1-PadC12)") (class "Default")
      (node (ref "IC5") (pin "C12") (pinfunction "PD1_C12") (pintype "bidirectional"))
    )
    (net (code "157") (name "unconnected-(IC5A-PD2-PadD12)") (class "Default")
      (node (ref "IC5") (pin "D12") (pinfunction "PD2_D12") (pintype "bidirectional"))
    )
    (net (code "158") (name "unconnected-(IC5A-PD3-PadD11)") (class "Default")
      (node (ref "IC5") (pin "D11") (pinfunction "PD3_D11") (pintype "bidirectional"))
    )
    (net (code "159") (name "unconnected-(IC5A-PD4-PadD10)") (class "Default")
      (node (ref "IC5") (pin "D10") (pinfunction "PD4_D10") (pintype "bidirectional"))
    )
    (net (code "160") (name "unconnected-(IC5A-PD6-PadB11)") (class "Default")
      (node (ref "IC5") (pin "B11") (pinfunction "PD6_B11") (pintype "bidirectional"))
    )
    (net (code "161") (name "unconnected-(IC5A-PD7-PadA11)") (class "Default")
      (node (ref "IC5") (pin "A11") (pinfunction "PD7_A11") (pintype "bidirectional"))
    )
    (net (code "162") (name "unconnected-(IC5A-PD11-PadN14)") (class "Default")
      (node (ref "IC5") (pin "N14") (pinfunction "PD11_N14") (pintype "bidirectional"))
    )
    (net (code "163") (name "unconnected-(IC5A-PD12-PadN13)") (class "Default")
      (node (ref "IC5") (pin "N13") (pinfunction "PD12_N13") (pintype "bidirectional"))
    )
    (net (code "164") (name "unconnected-(IC5A-PD14-PadM14)") (class "Default")
      (node (ref "IC5") (pin "M14") (pinfunction "PD14_M14") (pintype "bidirectional"))
    )
    (net (code "165") (name "unconnected-(IC5A-PD15-PadL14)") (class "Default")
      (node (ref "IC5") (pin "L14") (pinfunction "PD15_L14") (pintype "bidirectional"))
    )
    (net (code "166") (name "unconnected-(IC5B-PE0-PadA4)") (class "Default")
      (node (ref "IC5") (pin "A4") (pinfunction "PE0_A4") (pintype "bidirectional"))
    )
    (net (code "167") (name "unconnected-(IC5B-PE1-PadA3)") (class "Default")
      (node (ref "IC5") (pin "A3") (pinfunction "PE1_A3") (pintype "bidirectional"))
    )
    (net (code "168") (name "unconnected-(IC5B-PE2-PadA2)") (class "Default")
      (node (ref "IC5") (pin "A2") (pinfunction "PE2_A2") (pintype "bidirectional"))
    )
    (net (code "169") (name "unconnected-(IC5B-PE7-PadR8)") (class "Default")
      (node (ref "IC5") (pin "R8") (pinfunction "PE7_R8") (pintype "bidirectional"))
    )
    (net (code "170") (name "unconnected-(IC5B-PE8-PadP8)") (class "Default")
      (node (ref "IC5") (pin "P8") (pinfunction "PE8_P8") (pintype "bidirectional"))
    )
    (net (code "171") (name "unconnected-(IC5B-PE9-PadP9)") (class "Default")
      (node (ref "IC5") (pin "P9") (pinfunction "PE9_P9") (pintype "bidirectional"))
    )
    (net (code "172") (name "unconnected-(IC5B-PE10-PadR9)") (class "Default")
      (node (ref "IC5") (pin "R9") (pinfunction "PE10_R9") (pintype "bidirectional"))
    )
    (net (code "173") (name "unconnected-(IC5B-PE11-PadP10)") (class "Default")
      (node (ref "IC5") (pin "P10") (pinfunction "PE11_P10") (pintype "bidirectional"))
    )
    (net (code "174") (name "unconnected-(IC5B-PE12-PadR10)") (class "Default")
      (node (ref "IC5") (pin "R10") (pinfunction "PE12_R10") (pintype "bidirectional"))
    )
    (net (code "175") (name "unconnected-(IC5B-PE13-PadN11)") (class "Default")
      (node (ref "IC5") (pin "N11") (pinfunction "PE13_N11") (pintype "bidirectional"))
    )
    (net (code "176") (name "unconnected-(IC5B-PE14-PadP11)") (class "Default")
      (node (ref "IC5") (pin "P11") (pinfunction "PE14_P11") (pintype "bidirectional"))
    )
    (net (code "177") (name "unconnected-(IC5B-PF0-PadE2)") (class "Default")
      (node (ref "IC5") (pin "E2") (pinfunction "PF0_E2") (pintype "bidirectional"))
    )
    (net (code "178") (name "unconnected-(IC5B-PF1-PadH3)") (class "Default")
      (node (ref "IC5") (pin "H3") (pinfunction "PF1_H3") (pintype "bidirectional"))
    )
    (net (code "179") (name "unconnected-(IC5B-PF2-PadH2)") (class "Default")
      (node (ref "IC5") (pin "H2") (pinfunction "PF2_H2") (pintype "bidirectional"))
    )
    (net (code "180") (name "unconnected-(IC5B-PF3-PadJ2)") (class "Default")
      (node (ref "IC5") (pin "J2") (pinfunction "PF3_J2") (pintype "bidirectional"))
    )
    (net (code "181") (name "unconnected-(IC5B-PF4-PadJ3)") (class "Default")
      (node (ref "IC5") (pin "J3") (pinfunction "PF4_J3") (pintype "bidirectional"))
    )
    (net (code "182") (name "unconnected-(IC5B-PF5-PadK3)") (class "Default")
      (node (ref "IC5") (pin "K3") (pinfunction "PF5_K3") (pintype "bidirectional"))
    )
    (net (code "183") (name "unconnected-(IC5B-PF6-PadK2)") (class "Default")
      (node (ref "IC5") (pin "K2") (pinfunction "PF6_K2") (pintype "bidirectional"))
    )
    (net (code "184") (name "unconnected-(IC5B-PF8-PadL3)") (class "Default")
      (node (ref "IC5") (pin "L3") (pinfunction "PF8_L3") (pintype "bidirectional"))
    )
    (net (code "185") (name "unconnected-(IC5B-PF9-PadL2)") (class "Default")
      (node (ref "IC5") (pin "L2") (pinfunction "PF9_L2") (pintype "bidirectional"))
    )
    (net (code "186") (name "unconnected-(IC5B-PF10-PadL1)") (class "Default")
      (node (ref "IC5") (pin "L1") (pinfunction "PF10_L1") (pintype "bidirectional"))
    )
    (net (code "187") (name "unconnected-(IC5B-PF11-PadR6)") (class "Default")
      (node (ref "IC5") (pin "R6") (pinfunction "PF11_R6") (pintype "bidirectional"))
    )
    (net (code "188") (name "unconnected-(IC5B-PF12-PadP6)") (class "Default")
      (node (ref "IC5") (pin "P6") (pinfunction "PF12_P6") (pintype "bidirectional"))
    )
    (net (code "189") (name "unconnected-(IC5B-PF13-PadN6)") (class "Default")
      (node (ref "IC5") (pin "N6") (pinfunction "PF13_N6") (pintype "bidirectional"))
    )
    (net (code "190") (name "unconnected-(IC5B-PF14-PadR7)") (class "Default")
      (node (ref "IC5") (pin "R7") (pinfunction "PF14_R7") (pintype "bidirectional"))
    )
    (net (code "191") (name "unconnected-(IC5B-PF15-PadP7)") (class "Default")
      (node (ref "IC5") (pin "P7") (pinfunction "PF15_P7") (pintype "bidirectional"))
    )
    (net (code "192") (name "unconnected-(IC5B-PG0-PadN7)") (class "Default")
      (node (ref "IC5") (pin "N7") (pinfunction "PG0_N7") (pintype "bidirectional"))
    )
    (net (code "193") (name "unconnected-(IC5B-PG1-PadM7)") (class "Default")
      (node (ref "IC5") (pin "M7") (pinfunction "PG1_M7") (pintype "bidirectional"))
    )
    (net (code "194") (name "unconnected-(IC5B-PG4-PadK14)") (class "Default")
      (node (ref "IC5") (pin "K14") (pinfunction "PG4_K14") (pintype "bidirectional"))
    )
    (net (code "195") (name "unconnected-(IC5B-PG5-PadK13)") (class "Default")
      (node (ref "IC5") (pin "K13") (pinfunction "PG5_K13") (pintype "bidirectional"))
    )
    (net (code "196") (name "unconnected-(IC5B-PG7-PadJ14)") (class "Default")
      (node (ref "IC5") (pin "J14") (pinfunction "PG7_J14") (pintype "bidirectional"))
    )
    (net (code "197") (name "unconnected-(IC5B-PG8-PadH14)") (class "Default")
      (node (ref "IC5") (pin "H14") (pinfunction "PG8_H14") (pintype "bidirectional"))
    )
    (net (code "198") (name "unconnected-(IC5B-PG9-PadC10)") (class "Default")
      (node (ref "IC5") (pin "C10") (pinfunction "PG9_C10") (pintype "bidirectional"))
    )
    (net (code "199") (name "unconnected-(IC5B-PG10-PadB10)") (class "Default")
      (node (ref "IC5") (pin "B10") (pinfunction "PG10_B10") (pintype "bidirectional"))
    )
    (net (code "200") (name "unconnected-(IC5B-PG11-PadB9)") (class "Default")
      (node (ref "IC5") (pin "B9") (pinfunction "PG11_B9") (pintype "bidirectional"))
    )
    (net (code "201") (name "unconnected-(IC5B-PG12-PadB8)") (class "Default")
      (node (ref "IC5") (pin "B8") (pinfunction "PG12_B8") (pintype "bidirectional"))
    )
    (net (code "202") (name "unconnected-(IC5B-PG13-PadA8)") (class "Default")
      (node (ref "IC5") (pin "A8") (pinfunction "PG13_A8") (pintype "bidirectional"))
    )
    (net (code "203") (name "unconnected-(IC5B-PG14-PadA7)") (class "Default")
      (node (ref "IC5") (pin "A7") (pinfunction "PG14_A7") (pintype "bidirectional"))
    )
    (net (code "204") (name "unconnected-(IC5B-PG15-PadB7)") (class "Default")
      (node (ref "IC5") (pin "B7") (pinfunction "PG15_B7") (pintype "bidirectional"))
    )
    (net (code "205") (name "unconnected-(IC5B-PH2-PadF4)") (class "Default")
      (node (ref "IC5") (pin "F4") (pinfunction "PH2_F4") (pintype "bidirectional"))
    )
    (net (code "206") (name "unconnected-(IC5B-PH3-PadG4)") (class "Default")
      (node (ref "IC5") (pin "G4") (pinfunction "PH3_G4") (pintype "bidirectional"))
    )
    (net (code "207") (name "unconnected-(IC5B-PH4-PadH4)") (class "Default")
      (node (ref "IC5") (pin "H4") (pinfunction "PH4_H4") (pintype "bidirectional"))
    )
    (net (code "208") (name "unconnected-(IC5B-PH5-PadJ4)") (class "Default")
      (node (ref "IC5") (pin "J4") (pinfunction "PH5_J4") (pintype "bidirectional"))
    )
    (net (code "209") (name "unconnected-(IC5B-PH6-PadM11)") (class "Default")
      (node (ref "IC5") (pin "M11") (pinfunction "PH6_M11") (pintype "bidirectional"))
    )
    (net (code "210") (name "unconnected-(IC5B-PH7-PadN12)") (class "Default")
      (node (ref "IC5") (pin "N12") (pinfunction "PH7_N12") (pintype "bidirectional"))
    )
    (net (code "211") (name "unconnected-(IC5B-PH8-PadM12)") (class "Default")
      (node (ref "IC5") (pin "M12") (pinfunction "PH8_M12") (pintype "bidirectional"))
    )
    (net (code "212") (name "unconnected-(IC5B-PH9-PadM13)") (class "Default")
      (node (ref "IC5") (pin "M13") (pinfunction "PH9_M13") (pintype "bidirectional"))
    )
    (net (code "213") (name "unconnected-(IC5B-PH10-PadL13)") (class "Default")
      (node (ref "IC5") (pin "L13") (pinfunction "PH10_L13") (pintype "bidirectional"))
    )
    (net (code "214") (name "unconnected-(IC5B-PH11-PadL12)") (class "Default")
      (node (ref "IC5") (pin "L12") (pinfunction "PH11_L12") (pintype "bidirectional"))
    )
    (net (code "215") (name "unconnected-(IC5B-PH12-PadK12)") (class "Default")
      (node (ref "IC5") (pin "K12") (pinfunction "PH12_K12") (pintype "bidirectional"))
    )
    (net (code "216") (name "unconnected-(IC5B-PH13-PadE12)") (class "Default")
      (node (ref "IC5") (pin "E12") (pinfunction "PH13_E12") (pintype "bidirectional"))
    )
    (net (code "217") (name "unconnected-(IC5B-PH14-PadE13)") (class "Default")
      (node (ref "IC5") (pin "E13") (pinfunction "PH14_E13") (pintype "bidirectional"))
    )
    (net (code "218") (name "unconnected-(IC5B-PH15-PadD13)") (class "Default")
      (node (ref "IC5") (pin "D13") (pinfunction "PH15_D13") (pintype "bidirectional"))
    )
    (net (code "219") (name "unconnected-(IC5C-PI0-PadE14)") (class "Default")
      (node (ref "IC5") (pin "E14") (pinfunction "PI0_E14") (pintype "bidirectional"))
    )
    (net (code "220") (name "unconnected-(IC5C-PI1-PadD14)") (class "Default")
      (node (ref "IC5") (pin "D14") (pinfunction "PI1_D14") (pintype "bidirectional"))
    )
    (net (code "221") (name "unconnected-(IC5C-PI2-PadC14)") (class "Default")
      (node (ref "IC5") (pin "C14") (pinfunction "PI2_C14") (pintype "bidirectional"))
    )
    (net (code "222") (name "unconnected-(IC5C-PI3-PadC13)") (class "Default")
      (node (ref "IC5") (pin "C13") (pinfunction "PI3_C13") (pintype "bidirectional"))
    )
    (net (code "223") (name "unconnected-(IC5C-PI4-PadD4)") (class "Default")
      (node (ref "IC5") (pin "D4") (pinfunction "PI4_D4") (pintype "bidirectional"))
    )
    (net (code "224") (name "unconnected-(IC5C-PI5-PadC4)") (class "Default")
      (node (ref "IC5") (pin "C4") (pinfunction "PI5_C4") (pintype "bidirectional"))
    )
    (net (code "225") (name "unconnected-(IC5C-PI6-PadC3)") (class "Default")
      (node (ref "IC5") (pin "C3") (pinfunction "PI6_C3") (pintype "bidirectional"))
    )
    (net (code "226") (name "unconnected-(IC5C-PI7-PadC2)") (class "Default")
      (node (ref "IC5") (pin "C2") (pinfunction "PI7_C2") (pintype "bidirectional"))
    )
    (net (code "227") (name "unconnected-(IC5C-PI9-PadD3)") (class "Default")
      (node (ref "IC5") (pin "D3") (pinfunction "PI9_D3") (pintype "bidirectional"))
    )
    (net (code "228") (name "unconnected-(IC5C-PI10-PadE3)") (class "Default")
      (node (ref "IC5") (pin "E3") (pinfunction "PI10_E3") (pintype "bidirectional"))
    )
    (net (code "229") (name "unconnected-(IC5C-PI11-PadE4)") (class "Default")
      (node (ref "IC5") (pin "E4") (pinfunction "PI11_E4") (pintype "bidirectional"))
    )
    (net (code "230") (name "unconnected-(IC6-GND5-PadP1)") (class "Default")
      (node (ref "IC6") (pin "P1") (pinfunction "GND5_P1") (pintype "bidirectional"))
    )
    (net (code "231") (name "unconnected-(IC6-GND6-PadP2)") (class "Default")
      (node (ref "IC6") (pin "P2") (pinfunction "GND6_P2") (pintype "bidirectional"))
    )
    (net (code "232") (name "unconnected-(IC6-NC-Pad5)") (class "Default")
      (node (ref "IC6") (pin "5") (pinfunction "NC_5") (pintype "bidirectional"))
    )
    (net (code "233") (name "unconnected-(IC8-BYPASS-Pad4)") (class "Default")
      (node (ref "IC8") (pin "4") (pinfunction "BYPASS_4") (pintype "input"))
    )
    (net (code "234") (name "unconnected-(IC9-BYPASS-Pad4)") (class "Default")
      (node (ref "IC9") (pin "4") (pinfunction "BYPASS_4") (pintype "input"))
    )
    (net (code "235") (name "unconnected-(IC12-PG-Pad14)") (class "Default")
      (node (ref "IC12") (pin "14") (pinfunction "PG_14") (pintype "bidirectional"))
    )
    (net (code "236") (name "unconnected-(IC13-NC1-Pad4)") (class "Default")
      (node (ref "IC13") (pin "4") (pinfunction "NC1_4") (pintype "bidirectional"))
    )
    (net (code "237") (name "unconnected-(IC13-NC2-Pad7)") (class "Default")
      (node (ref "IC13") (pin "7") (pinfunction "NC2_7") (pintype "bidirectional"))
    )
    (net (code "238") (name "unconnected-(IC13-NC3-Pad8)") (class "Default")
      (node (ref "IC13") (pin "8") (pinfunction "NC3_8") (pintype "bidirectional"))
    )
    (net (code "239") (name "unconnected-(IC13-NC4-Pad9)") (class "Default")
      (node (ref "IC13") (pin "9") (pinfunction "NC4_9") (pintype "bidirectional"))
    )
    (net (code "240") (name "unconnected-(IC13-NC5-Pad10)") (class "Default")
      (node (ref "IC13") (pin "10") (pinfunction "NC5_10") (pintype "bidirectional"))
    )
    (net (code "241") (name "unconnected-(IC13-NC6-Pad11)") (class "Default")
      (node (ref "IC13") (pin "11") (pinfunction "NC6_11") (pintype "bidirectional"))
    )
    (net (code "242") (name "unconnected-(IC13-NC7-Pad12)") (class "Default")
      (node (ref "IC13") (pin "12") (pinfunction "NC7_12") (pintype "bidirectional"))
    )
    (net (code "243") (name "unconnected-(IC13-NC8-Pad20)") (class "Default")
      (node (ref "IC13") (pin "20") (pinfunction "NC8_20") (pintype "bidirectional"))
    )
    (net (code "244") (name "unconnected-(IC13-NC9-Pad21)") (class "Default")
      (node (ref "IC13") (pin "21") (pinfunction "NC9_21") (pintype "bidirectional"))
    )
    (net (code "245") (name "unconnected-(IC13-PWR_REF-Pad24)") (class "Default")
      (node (ref "IC13") (pin "24") (pinfunction "PWR_REF_24") (pintype "bidirectional"))
    )
    (net (code "246") (name "unconnected-(IC13-PWR_SENSE-Pad23)") (class "Default")
      (node (ref "IC13") (pin "23") (pinfunction "PWR_SENSE_23") (pintype "bidirectional"))
    )
    (net (code "247") (name "unconnected-(IC14-BYPASS-Pad4)") (class "Default")
      (node (ref "IC14") (pin "4") (pinfunction "BYPASS_4") (pintype "input"))
    )
    (net (code "248") (name "unconnected-(IC16-~{ALERT}-Pad7)") (class "Default")
      (node (ref "IC16") (pin "7") (pinfunction "~{ALERT}_7") (pintype "passive"))
    )
    (net (code "249") (name "unconnected-(U$1-RSV-Pad8)") (class "Default")
      (node (ref "U$1") (pin "8") (pinfunction "RSV_8") (pintype "bidirectional"))
    )
    (net (code "250") (name "unconnected-(X1A-S-Pad1)") (class "Default")
      (node (ref "X1") (pin "1") (pinfunction "S_1") (pintype "passive"))
    )
    (net (code "251") (name "unconnected-(X1L-S-Pad2)") (class "Default")
      (node (ref "X1") (pin "2") (pinfunction "S_2") (pintype "passive"))
    )
    (net (code "252") (name "unconnected-(X1Q-S-Pad24)") (class "Default")
      (node (ref "X1") (pin "24") (pinfunction "S_24") (pintype "passive"))
    )
  )
)
